# NN22_RPi_DetAdapter01_s00.net
KiCad netlist of a schematic drawn in EAGLE
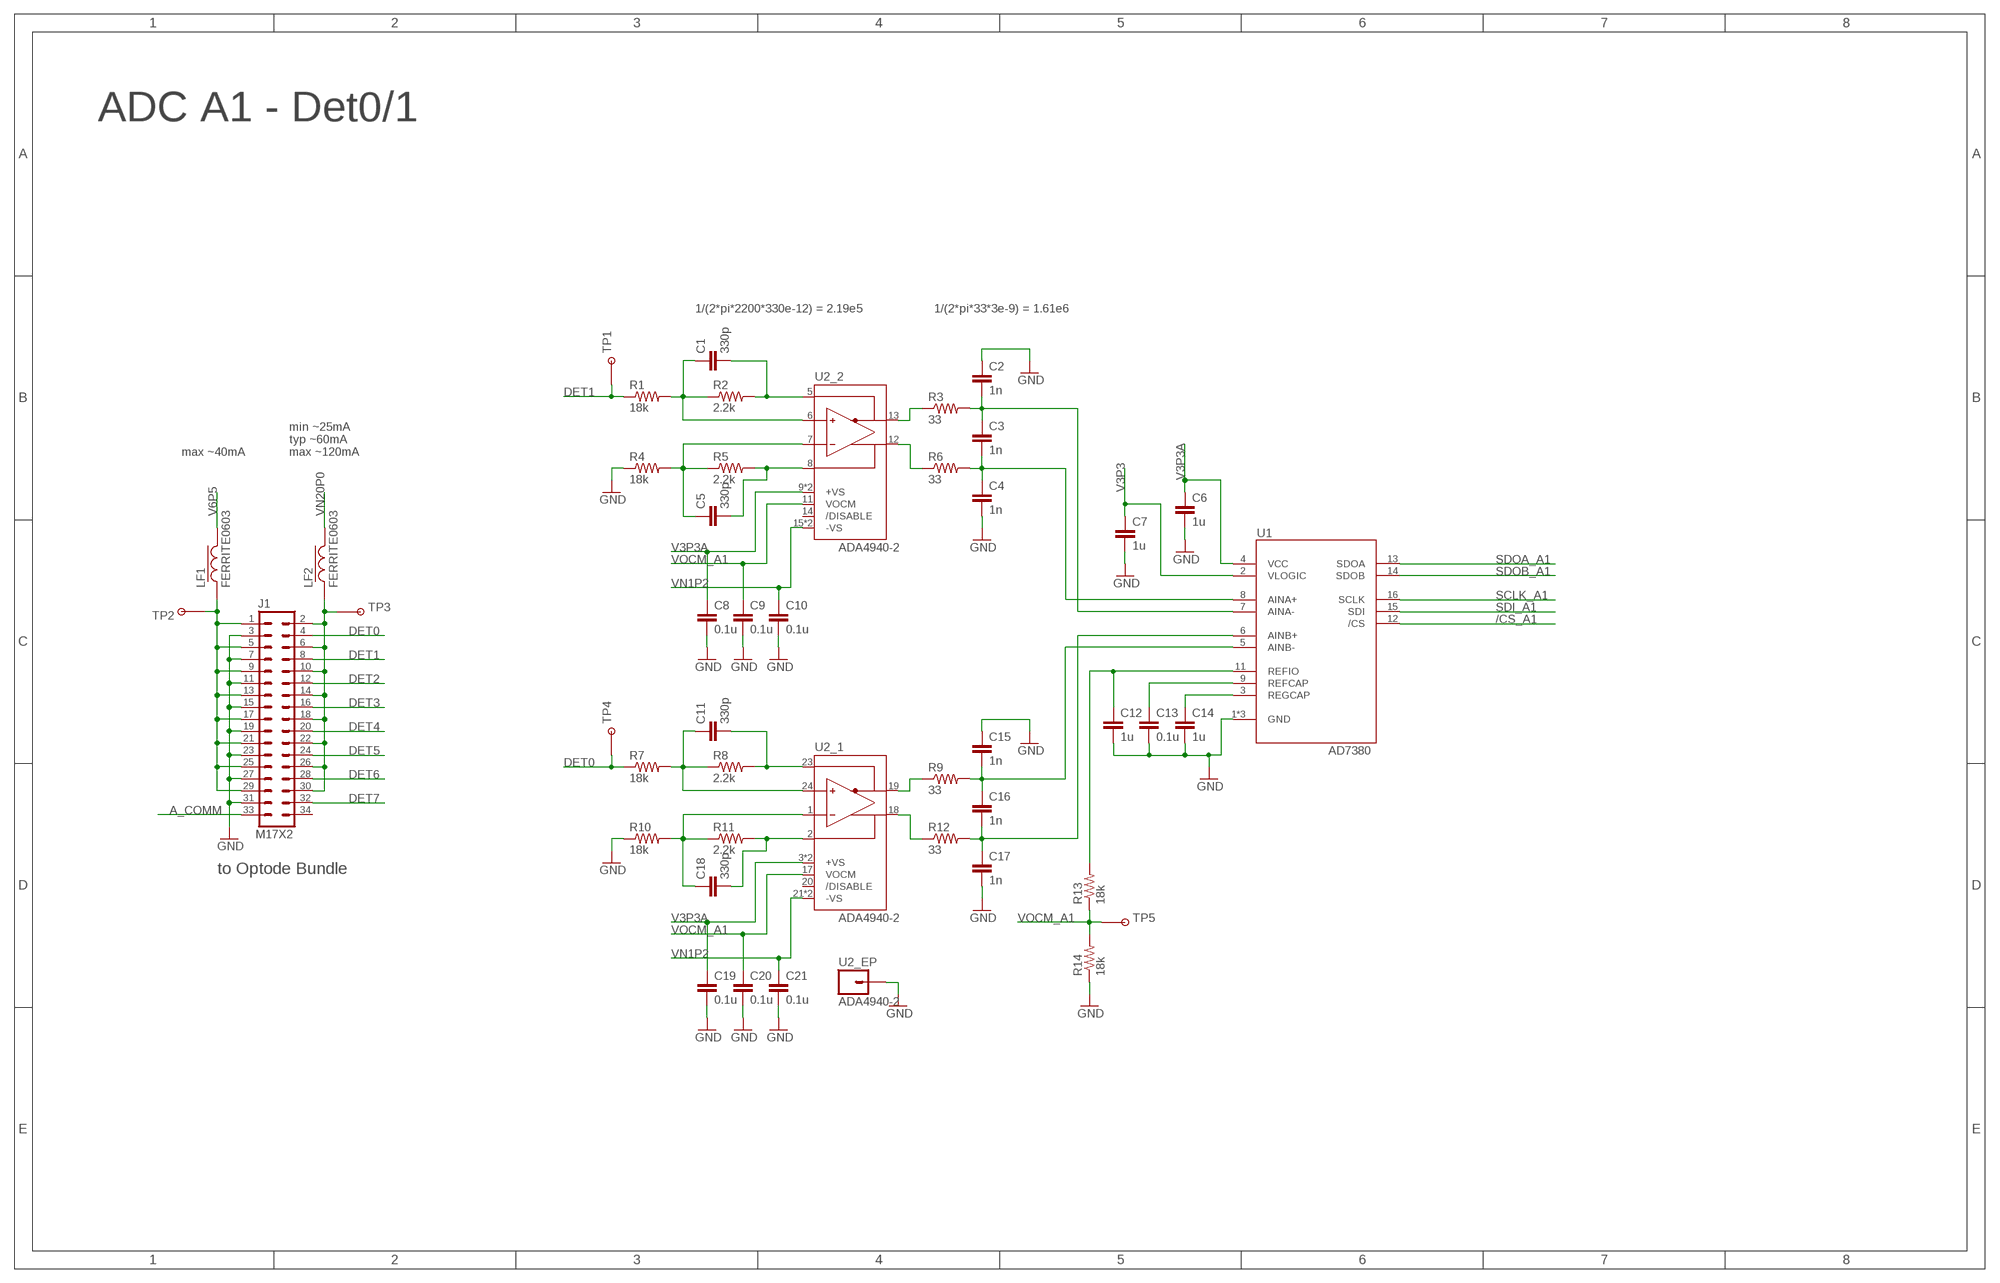
[diagram p0: schematic, sheet 1]
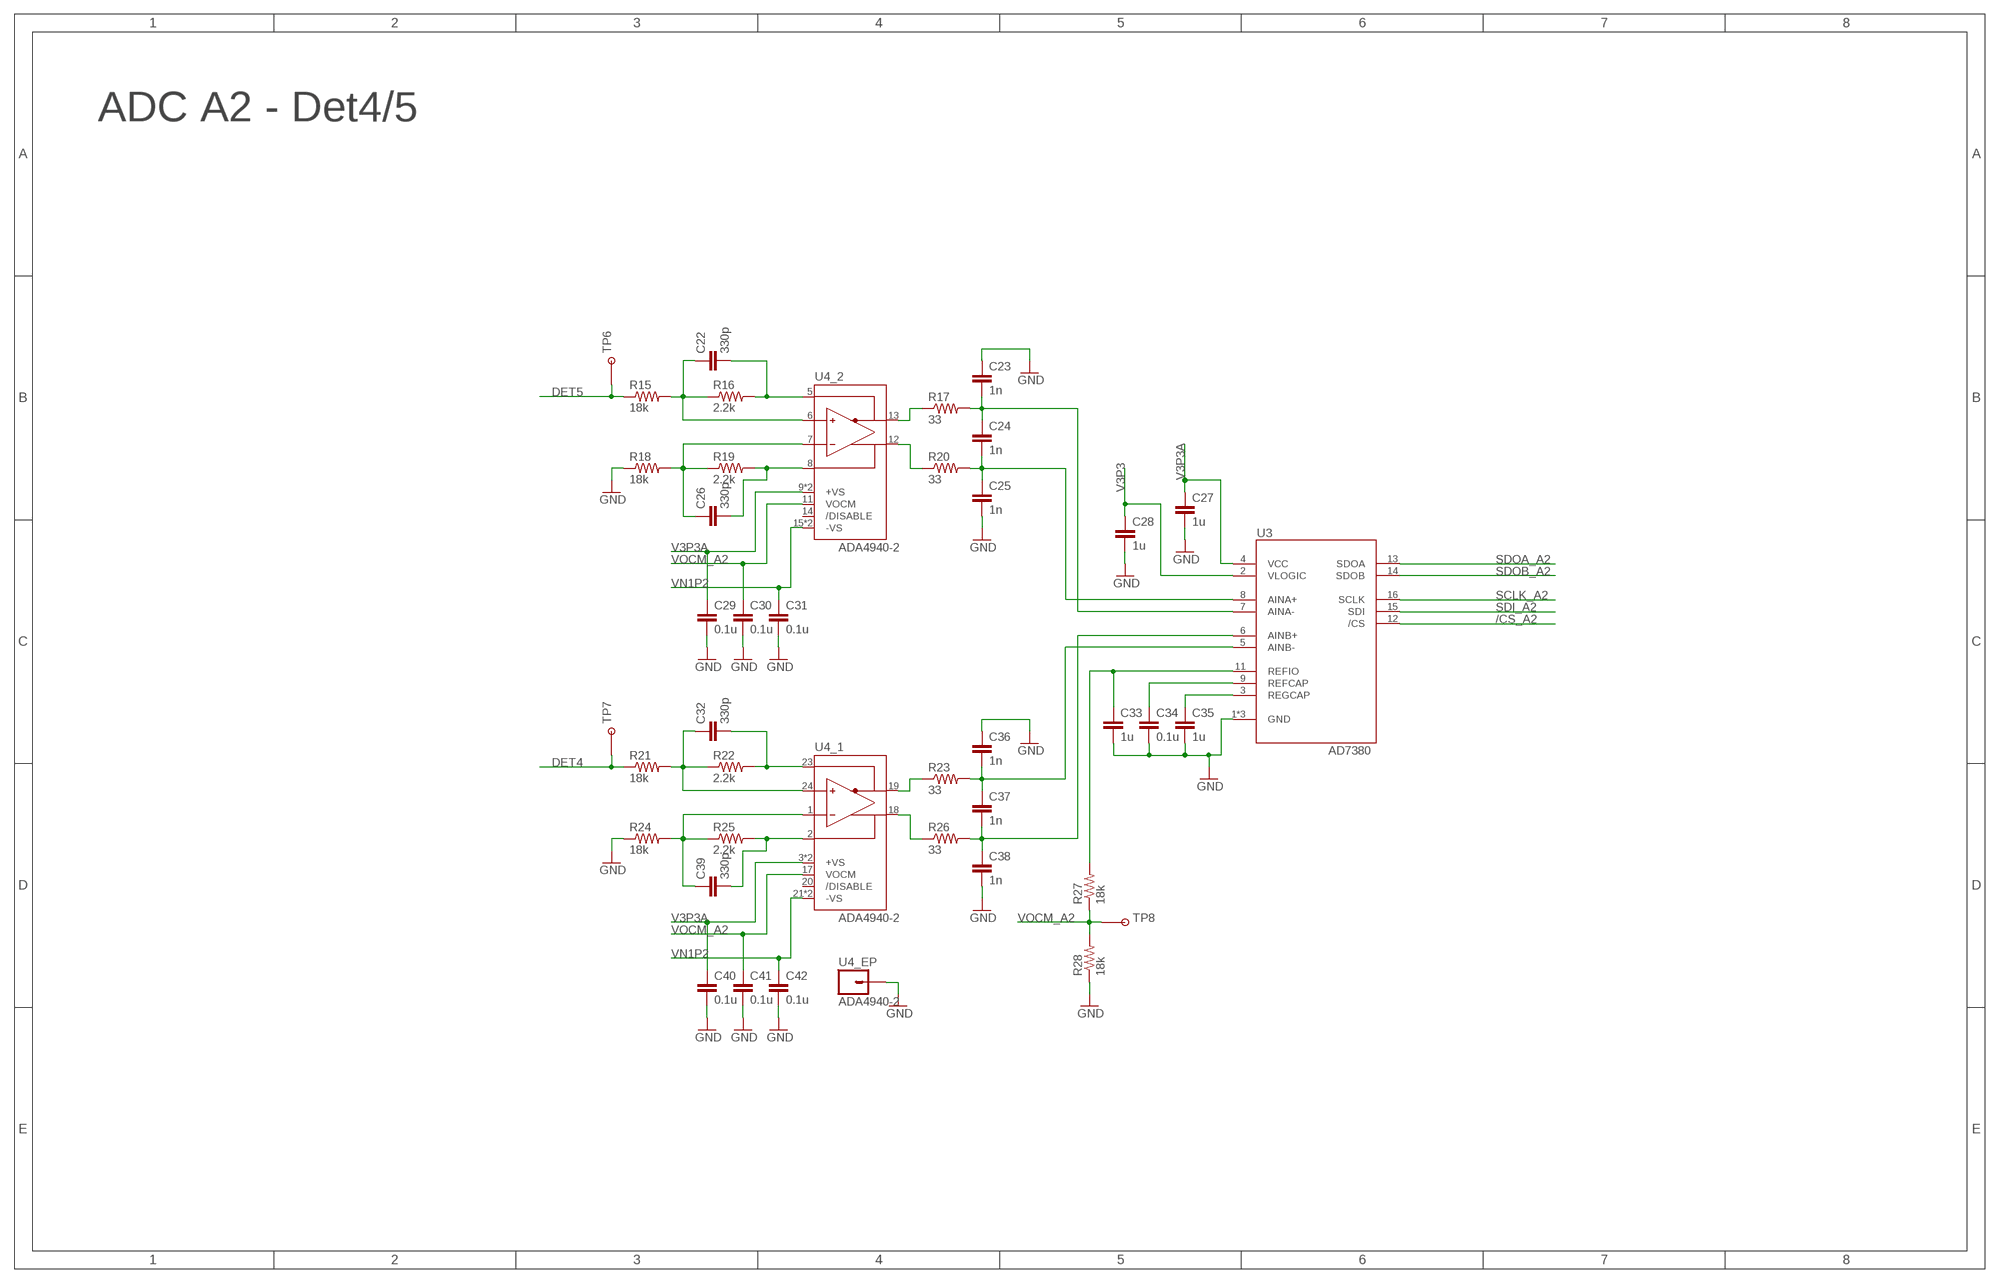
[diagram p1: schematic, sheet 2]
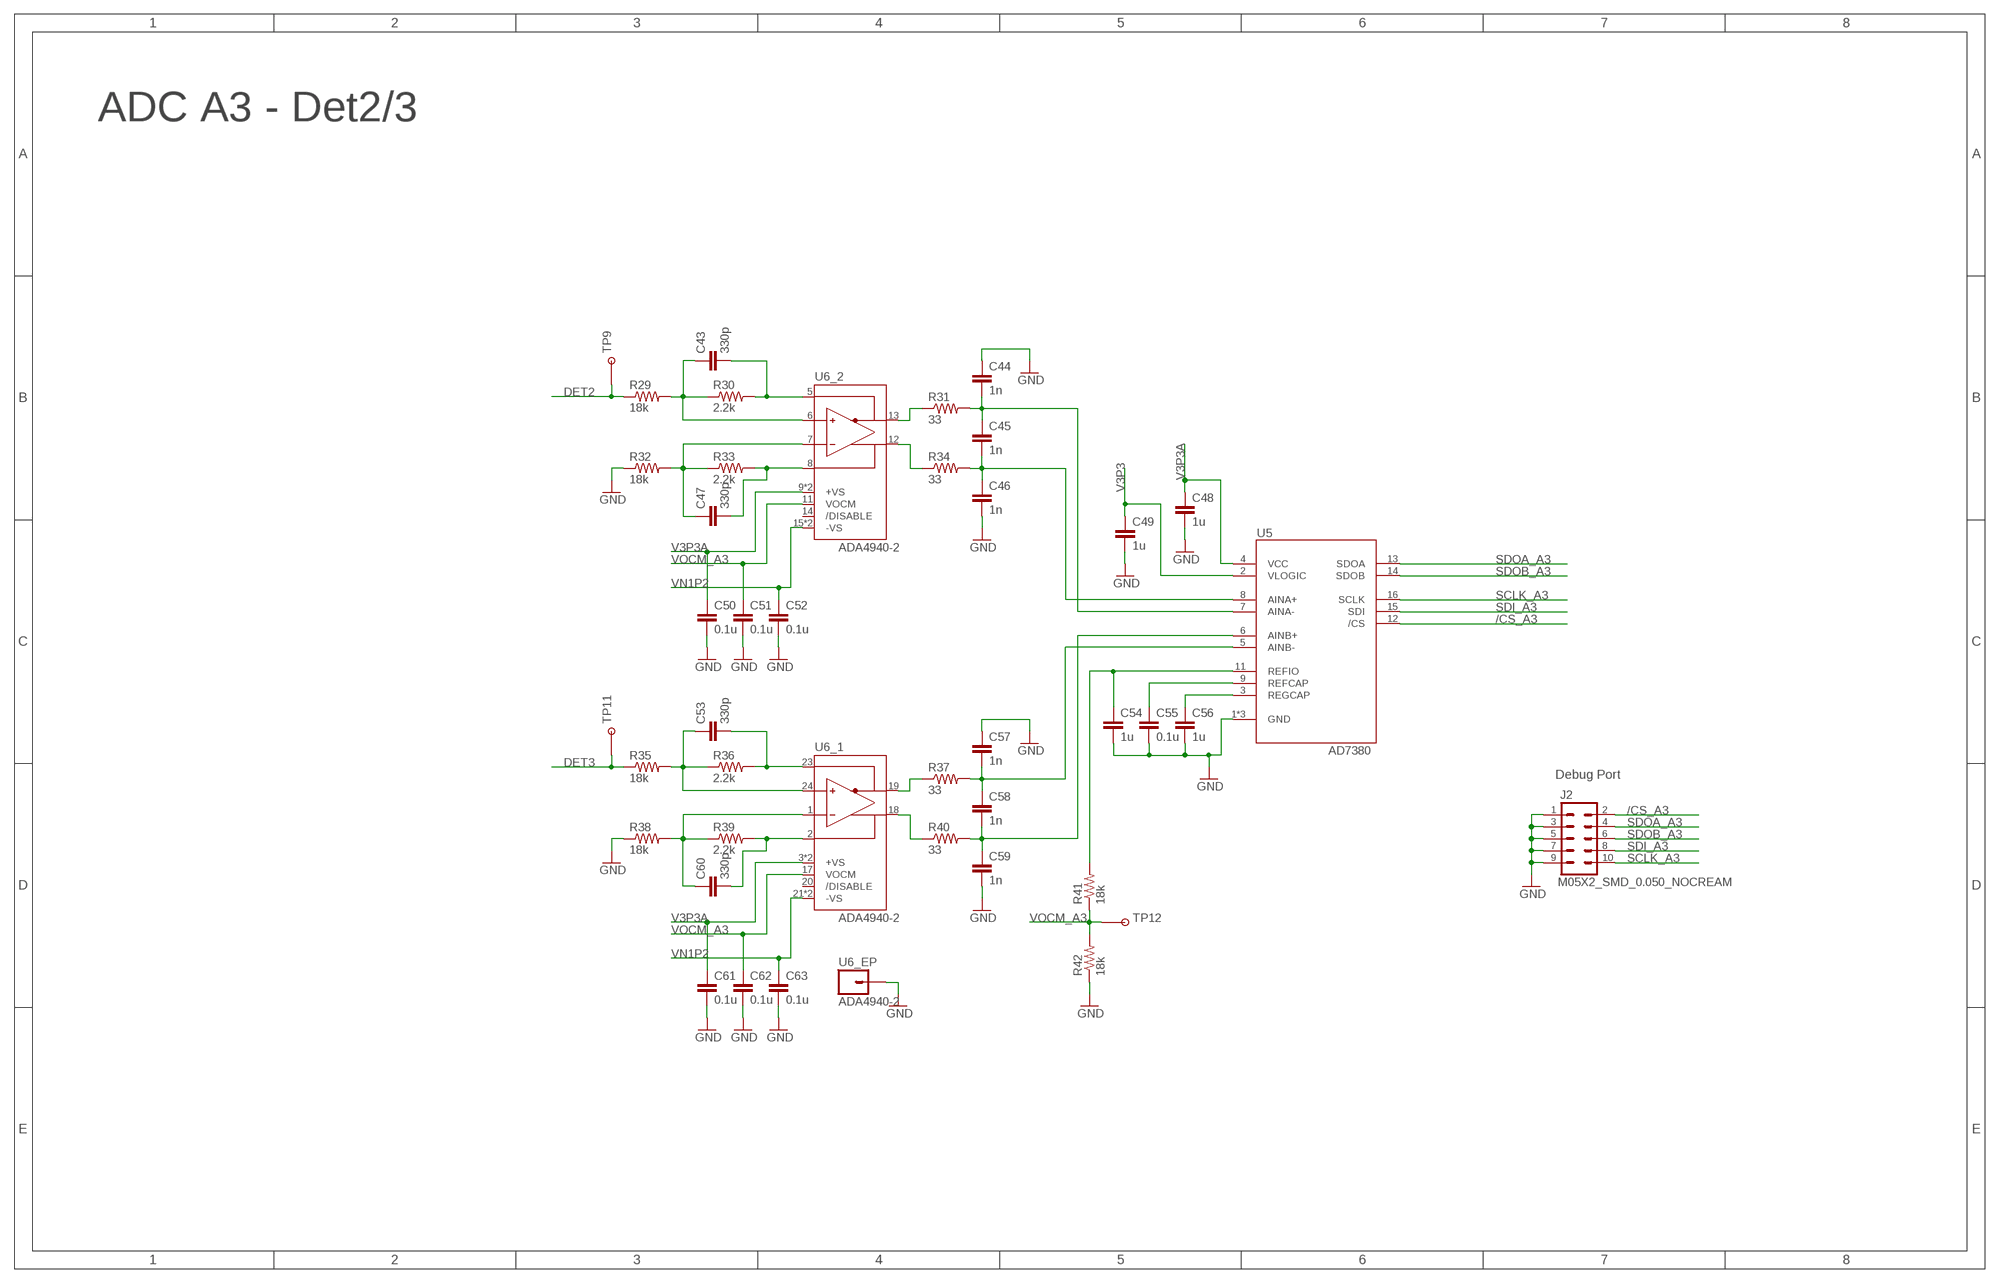
[diagram p2: schematic, sheet 3]
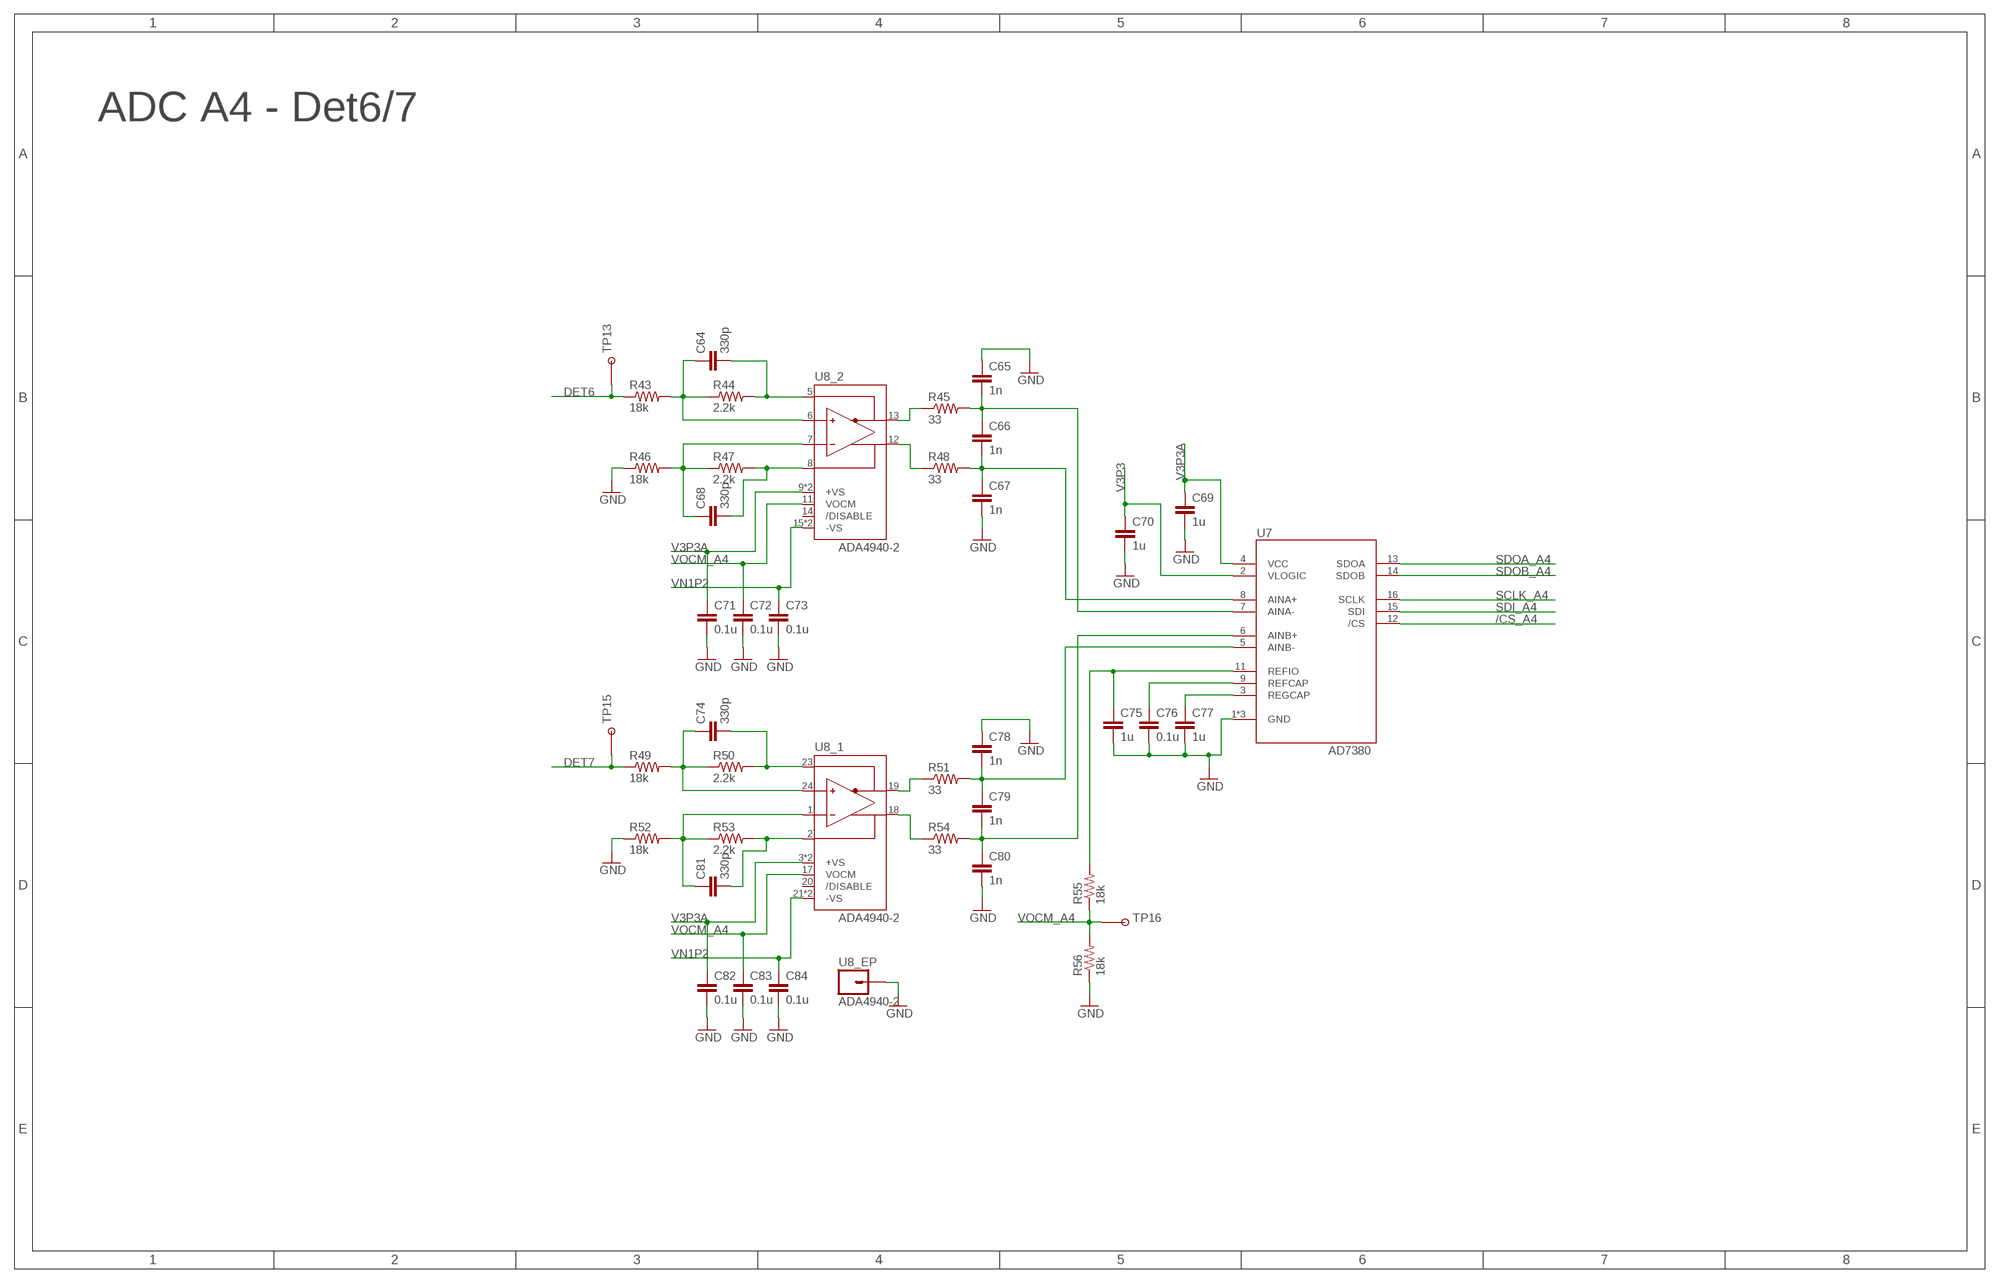
[diagram p3: schematic, sheet 4]
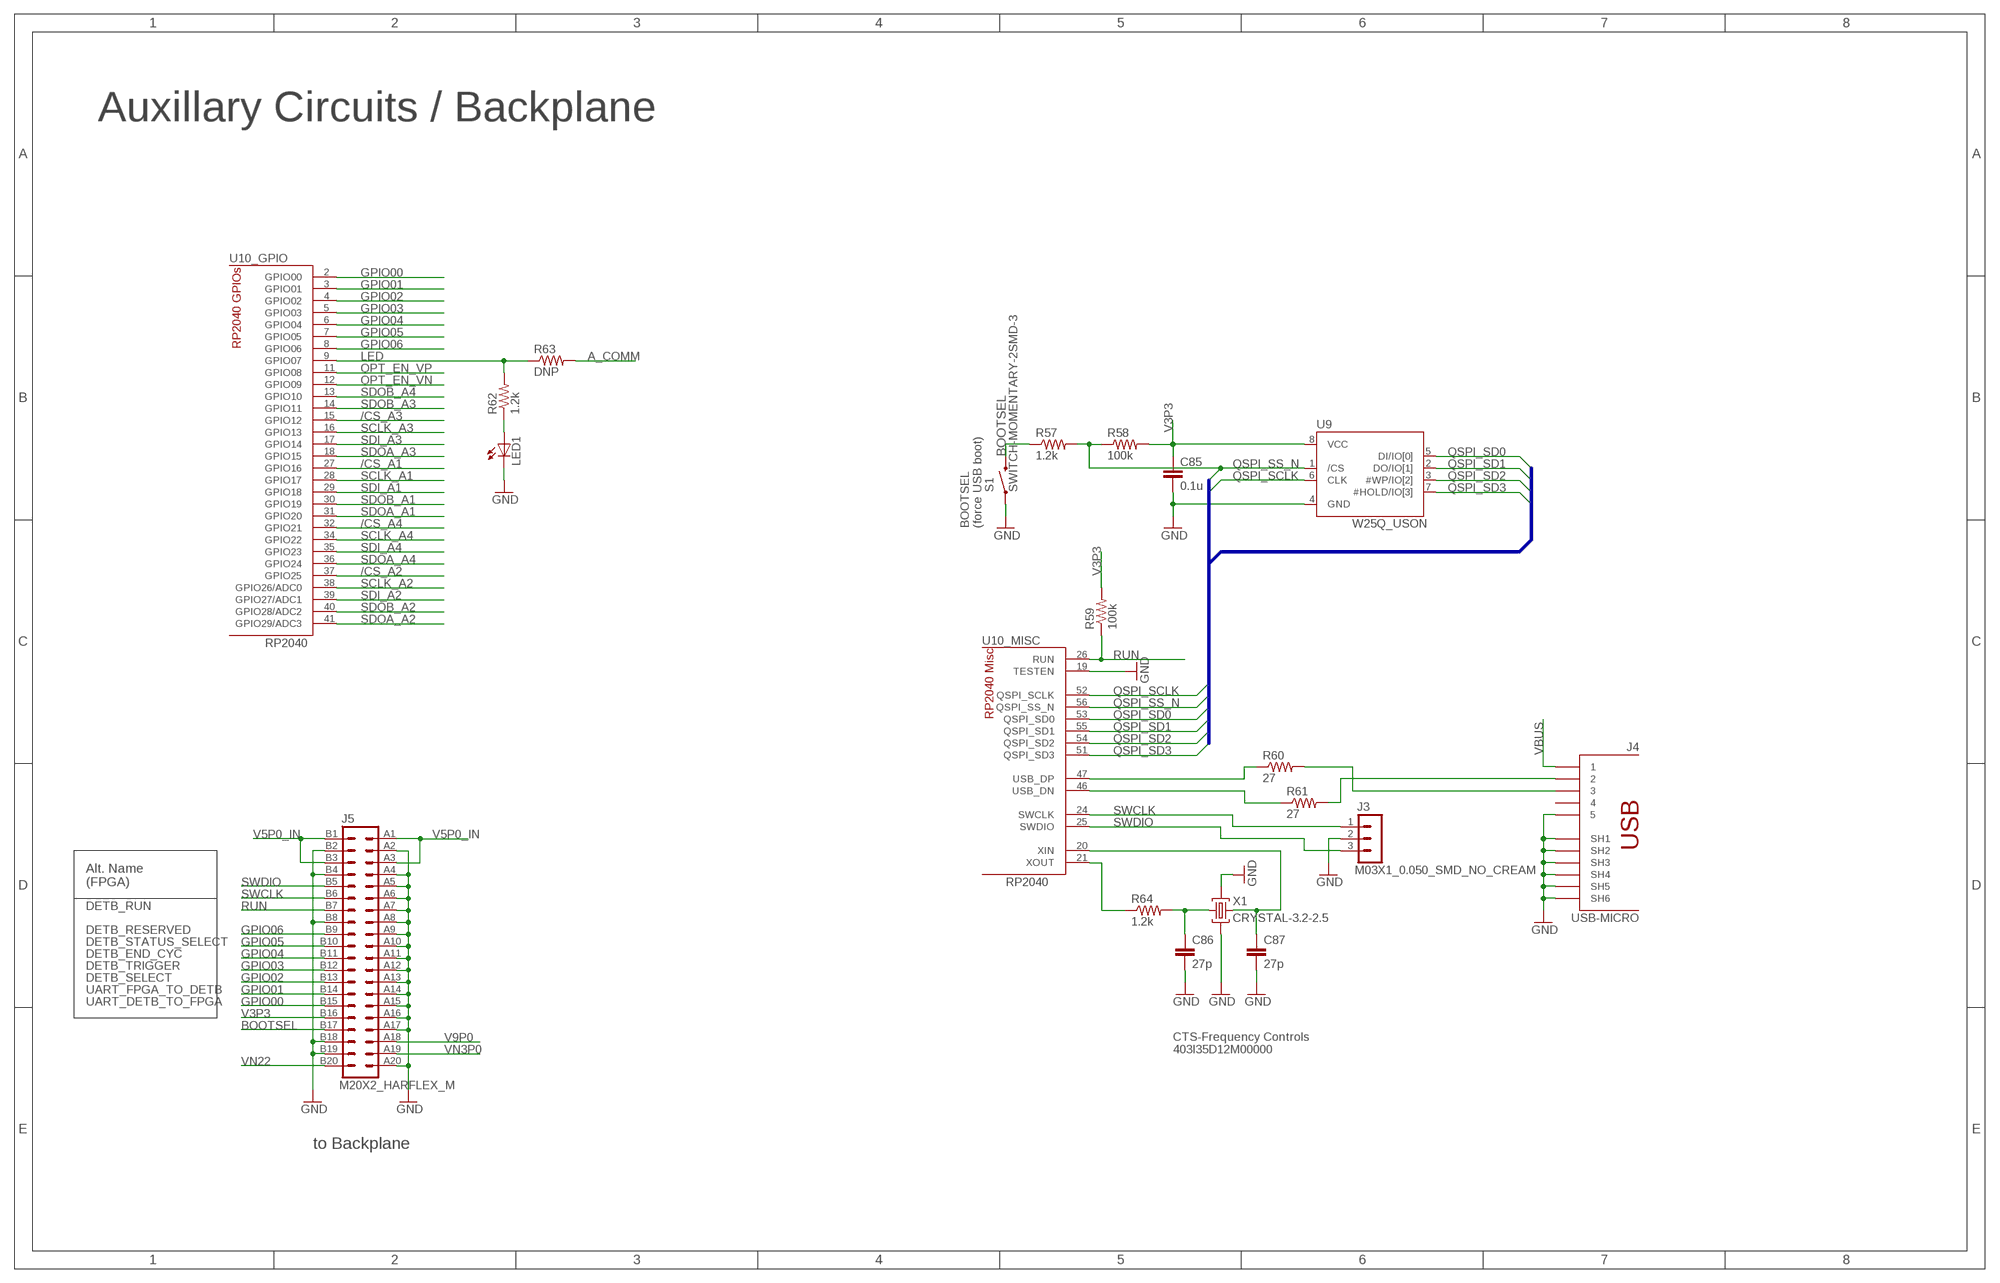
[diagram p4: schematic, sheet 5]
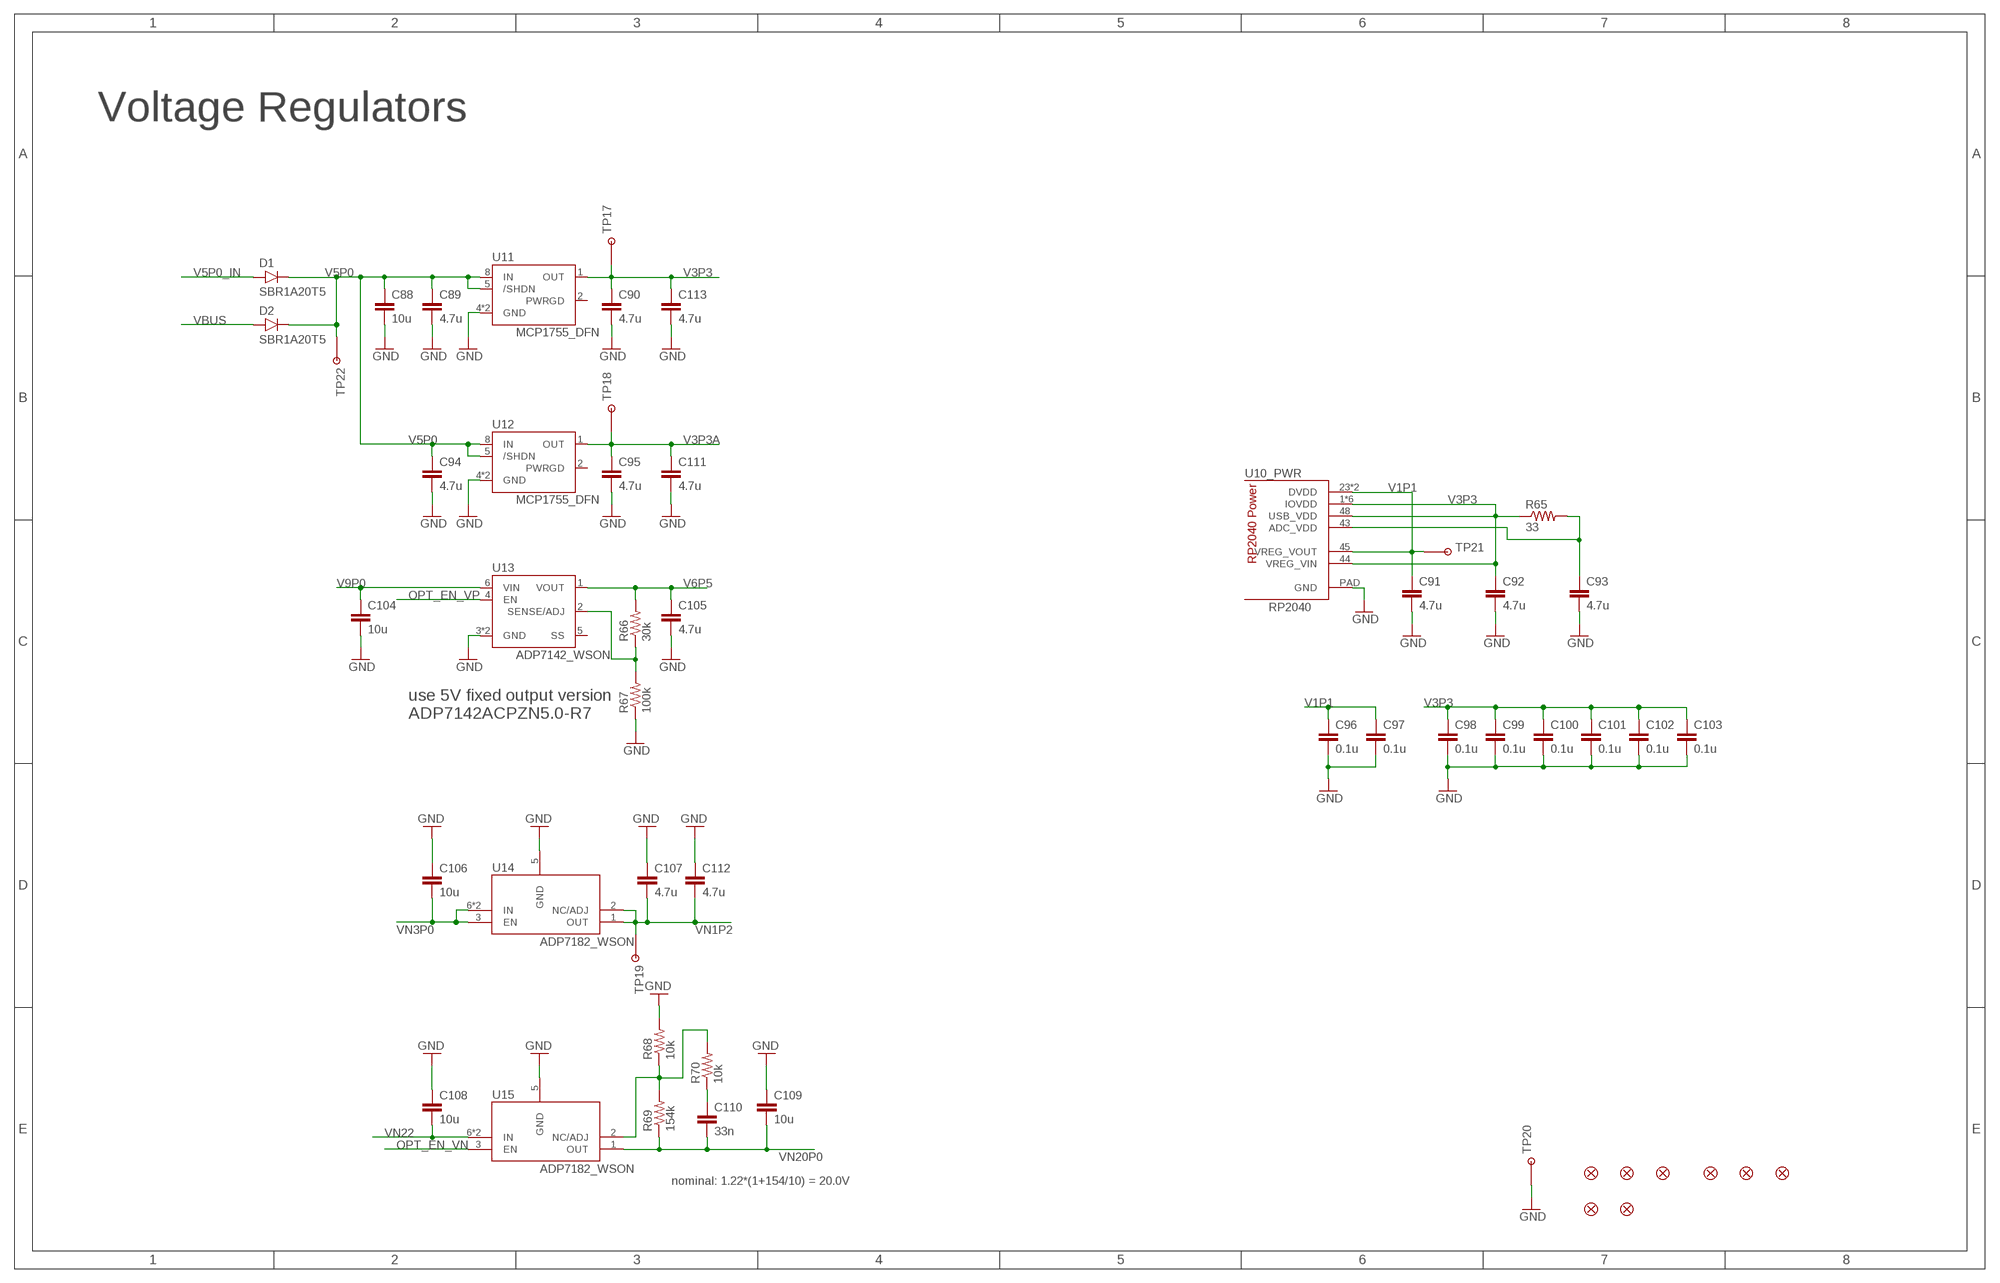
[diagram p5: schematic, sheet 6]

(export (version "E")
  (design (tool "Eeschema 10.0.6"))
  (components
    (comp (ref "C1")
      (value "330p")
      (footprint "eagle-import:0402-CAP")
      (libsource (lib "eagle-import") (part "CAP0402-CAP"))
    )
    (comp (ref "C2")
      (value "1n")
      (footprint "eagle-import:0402-CAP")
      (libsource (lib "eagle-import") (part "CAP0402-CAP"))
    )
    (comp (ref "C3")
      (value "1n")
      (footprint "eagle-import:0402-CAP")
      (libsource (lib "eagle-import") (part "CAP0402-CAP"))
    )
    (comp (ref "C4")
      (value "1n")
      (footprint "eagle-import:0402-CAP")
      (libsource (lib "eagle-import") (part "CAP0402-CAP"))
    )
    (comp (ref "C5")
      (value "330p")
      (footprint "eagle-import:0402-CAP")
      (libsource (lib "eagle-import") (part "CAP0402-CAP"))
    )
    (comp (ref "C6")
      (value "1u")
      (footprint "eagle-import:0402-CAP")
      (libsource (lib "eagle-import") (part "CAP0402-CAP"))
    )
    (comp (ref "C7")
      (value "1u")
      (footprint "eagle-import:0402-CAP")
      (libsource (lib "eagle-import") (part "CAP0402-CAP"))
    )
    (comp (ref "C8")
      (value "0.1u")
      (footprint "eagle-import:0402-CAP")
      (libsource (lib "eagle-import") (part "CAP0402-CAP"))
    )
    (comp (ref "C9")
      (value "0.1u")
      (footprint "eagle-import:0402-CAP")
      (libsource (lib "eagle-import") (part "CAP0402-CAP"))
    )
    (comp (ref "C10")
      (value "0.1u")
      (footprint "eagle-import:0402-CAP")
      (libsource (lib "eagle-import") (part "CAP0402-CAP"))
    )
    (comp (ref "C11")
      (value "330p")
      (footprint "eagle-import:0402-CAP")
      (libsource (lib "eagle-import") (part "CAP0402-CAP"))
    )
    (comp (ref "C12")
      (value "1u")
      (footprint "eagle-import:0402-CAP")
      (libsource (lib "eagle-import") (part "CAP0402-CAP"))
    )
    (comp (ref "C13")
      (value "0.1u")
      (footprint "eagle-import:0402-CAP")
      (libsource (lib "eagle-import") (part "CAP0402-CAP"))
    )
    (comp (ref "C14")
      (value "1u")
      (footprint "eagle-import:0402-CAP")
      (libsource (lib "eagle-import") (part "CAP0402-CAP"))
    )
    (comp (ref "C15")
      (value "1n")
      (footprint "eagle-import:0402-CAP")
      (libsource (lib "eagle-import") (part "CAP0402-CAP"))
    )
    (comp (ref "C16")
      (value "1n")
      (footprint "eagle-import:0402-CAP")
      (libsource (lib "eagle-import") (part "CAP0402-CAP"))
    )
    (comp (ref "C17")
      (value "1n")
      (footprint "eagle-import:0402-CAP")
      (libsource (lib "eagle-import") (part "CAP0402-CAP"))
    )
    (comp (ref "C18")
      (value "330p")
      (footprint "eagle-import:0402-CAP")
      (libsource (lib "eagle-import") (part "CAP0402-CAP"))
    )
    (comp (ref "C19")
      (value "0.1u")
      (footprint "eagle-import:0402-CAP")
      (libsource (lib "eagle-import") (part "CAP0402-CAP"))
    )
    (comp (ref "C20")
      (value "0.1u")
      (footprint "eagle-import:0402-CAP")
      (libsource (lib "eagle-import") (part "CAP0402-CAP"))
    )
    (comp (ref "C21")
      (value "0.1u")
      (footprint "eagle-import:0402-CAP")
      (libsource (lib "eagle-import") (part "CAP0402-CAP"))
    )
    (comp (ref "J1")
      (value "M17X2")
      (footprint "eagle-import:M17X2_0.050_SHF")
      (libsource (lib "eagle-import") (part "M17X2"))
    )
    (comp (ref "LF1")
      (value "FERRITE0603")
      (footprint "eagle-import:0603-FER")
      (libsource (lib "eagle-import") (part "FERRITE0603"))
    )
    (comp (ref "LF2")
      (value "FERRITE0603")
      (footprint "eagle-import:0603-FER")
      (libsource (lib "eagle-import") (part "FERRITE0603"))
    )
    (comp (ref "R1")
      (value "18k")
      (footprint "eagle-import:0402-RES")
      (libsource (lib "eagle-import") (part "RESISTOR0402-RES"))
    )
    (comp (ref "R2")
      (value "2.2k")
      (footprint "eagle-import:0402-RES")
      (libsource (lib "eagle-import") (part "RESISTOR0402-RES"))
    )
    (comp (ref "R3")
      (value "33")
      (footprint "eagle-import:0402-RES")
      (libsource (lib "eagle-import") (part "RESISTOR0402-RES"))
    )
    (comp (ref "R4")
      (value "18k")
      (footprint "eagle-import:0402-RES")
      (libsource (lib "eagle-import") (part "RESISTOR0402-RES"))
    )
    (comp (ref "R5")
      (value "2.2k")
      (footprint "eagle-import:0402-RES")
      (libsource (lib "eagle-import") (part "RESISTOR0402-RES"))
    )
    (comp (ref "R6")
      (value "33")
      (footprint "eagle-import:0402-RES")
      (libsource (lib "eagle-import") (part "RESISTOR0402-RES"))
    )
    (comp (ref "R7")
      (value "18k")
      (footprint "eagle-import:0402-RES")
      (libsource (lib "eagle-import") (part "RESISTOR0402-RES"))
    )
    (comp (ref "R8")
      (value "2.2k")
      (footprint "eagle-import:0402-RES")
      (libsource (lib "eagle-import") (part "RESISTOR0402-RES"))
    )
    (comp (ref "R9")
      (value "33")
      (footprint "eagle-import:0402-RES")
      (libsource (lib "eagle-import") (part "RESISTOR0402-RES"))
    )
    (comp (ref "R10")
      (value "18k")
      (footprint "eagle-import:0402-RES")
      (libsource (lib "eagle-import") (part "RESISTOR0402-RES"))
    )
    (comp (ref "R11")
      (value "2.2k")
      (footprint "eagle-import:0402-RES")
      (libsource (lib "eagle-import") (part "RESISTOR0402-RES"))
    )
    (comp (ref "R12")
      (value "33")
      (footprint "eagle-import:0402-RES")
      (libsource (lib "eagle-import") (part "RESISTOR0402-RES"))
    )
    (comp (ref "R13")
      (value "18k")
      (footprint "eagle-import:0402-RES")
      (libsource (lib "eagle-import") (part "RESISTOR0402-RES"))
    )
    (comp (ref "R14")
      (value "18k")
      (footprint "eagle-import:0402-RES")
      (libsource (lib "eagle-import") (part "RESISTOR0402-RES"))
    )
    (comp (ref "TP1")
      (value "TESTPOINT_ROUND")
      (footprint "eagle-import:TESTPAD_ROUND")
      (libsource (lib "eagle-import") (part "TESTPOINT_ROUND"))
    )
    (comp (ref "TP2")
      (value "TESTPOINT_ROUND")
      (footprint "eagle-import:TESTPAD_ROUND")
      (libsource (lib "eagle-import") (part "TESTPOINT_ROUND"))
    )
    (comp (ref "TP3")
      (value "TESTPOINT_ROUND")
      (footprint "eagle-import:TESTPAD_ROUND")
      (libsource (lib "eagle-import") (part "TESTPOINT_ROUND"))
    )
    (comp (ref "TP4")
      (value "TESTPOINT_ROUND")
      (footprint "eagle-import:TESTPAD_ROUND")
      (libsource (lib "eagle-import") (part "TESTPOINT_ROUND"))
    )
    (comp (ref "TP5")
      (value "TESTPOINT_ROUND")
      (footprint "eagle-import:TESTPAD_ROUND")
      (libsource (lib "eagle-import") (part "TESTPOINT_ROUND"))
    )
    (comp (ref "U1")
      (value "AD7380")
      (footprint "eagle-import:LFCSP16")
      (libsource (lib "eagle-import") (part "AD7380"))
    )
    (comp (ref "U2")
      (value "ADA4940-2")
      (footprint "eagle-import:LFCSP24")
      (libsource (lib "eagle-import") (part "ADA4940-2"))
    )
    (comp (ref "C64")
      (value "330p")
      (footprint "eagle-import:0402-CAP")
      (libsource (lib "eagle-import") (part "CAP0402-CAP"))
    )
    (comp (ref "C65")
      (value "1n")
      (footprint "eagle-import:0402-CAP")
      (libsource (lib "eagle-import") (part "CAP0402-CAP"))
    )
    (comp (ref "C66")
      (value "1n")
      (footprint "eagle-import:0402-CAP")
      (libsource (lib "eagle-import") (part "CAP0402-CAP"))
    )
    (comp (ref "C67")
      (value "1n")
      (footprint "eagle-import:0402-CAP")
      (libsource (lib "eagle-import") (part "CAP0402-CAP"))
    )
    (comp (ref "C68")
      (value "330p")
      (footprint "eagle-import:0402-CAP")
      (libsource (lib "eagle-import") (part "CAP0402-CAP"))
    )
    (comp (ref "C69")
      (value "1u")
      (footprint "eagle-import:0402-CAP")
      (libsource (lib "eagle-import") (part "CAP0402-CAP"))
    )
    (comp (ref "C70")
      (value "1u")
      (footprint "eagle-import:0402-CAP")
      (libsource (lib "eagle-import") (part "CAP0402-CAP"))
    )
    (comp (ref "C71")
      (value "0.1u")
      (footprint "eagle-import:0402-CAP")
      (libsource (lib "eagle-import") (part "CAP0402-CAP"))
    )
    (comp (ref "C72")
      (value "0.1u")
      (footprint "eagle-import:0402-CAP")
      (libsource (lib "eagle-import") (part "CAP0402-CAP"))
    )
    (comp (ref "C73")
      (value "0.1u")
      (footprint "eagle-import:0402-CAP")
      (libsource (lib "eagle-import") (part "CAP0402-CAP"))
    )
    (comp (ref "C74")
      (value "330p")
      (footprint "eagle-import:0402-CAP")
      (libsource (lib "eagle-import") (part "CAP0402-CAP"))
    )
    (comp (ref "C75")
      (value "1u")
      (footprint "eagle-import:0402-CAP")
      (libsource (lib "eagle-import") (part "CAP0402-CAP"))
    )
    (comp (ref "C76")
      (value "0.1u")
      (footprint "eagle-import:0402-CAP")
      (libsource (lib "eagle-import") (part "CAP0402-CAP"))
    )
    (comp (ref "C77")
      (value "1u")
      (footprint "eagle-import:0402-CAP")
      (libsource (lib "eagle-import") (part "CAP0402-CAP"))
    )
    (comp (ref "C78")
      (value "1n")
      (footprint "eagle-import:0402-CAP")
      (libsource (lib "eagle-import") (part "CAP0402-CAP"))
    )
    (comp (ref "C79")
      (value "1n")
      (footprint "eagle-import:0402-CAP")
      (libsource (lib "eagle-import") (part "CAP0402-CAP"))
    )
    (comp (ref "C80")
      (value "1n")
      (footprint "eagle-import:0402-CAP")
      (libsource (lib "eagle-import") (part "CAP0402-CAP"))
    )
    (comp (ref "C81")
      (value "330p")
      (footprint "eagle-import:0402-CAP")
      (libsource (lib "eagle-import") (part "CAP0402-CAP"))
    )
    (comp (ref "C82")
      (value "0.1u")
      (footprint "eagle-import:0402-CAP")
      (libsource (lib "eagle-import") (part "CAP0402-CAP"))
    )
    (comp (ref "C83")
      (value "0.1u")
      (footprint "eagle-import:0402-CAP")
      (libsource (lib "eagle-import") (part "CAP0402-CAP"))
    )
    (comp (ref "C84")
      (value "0.1u")
      (footprint "eagle-import:0402-CAP")
      (libsource (lib "eagle-import") (part "CAP0402-CAP"))
    )
    (comp (ref "R43")
      (value "18k")
      (footprint "eagle-import:0402-RES")
      (libsource (lib "eagle-import") (part "RESISTOR0402-RES"))
    )
    (comp (ref "R44")
      (value "2.2k")
      (footprint "eagle-import:0402-RES")
      (libsource (lib "eagle-import") (part "RESISTOR0402-RES"))
    )
    (comp (ref "R45")
      (value "33")
      (footprint "eagle-import:0402-RES")
      (libsource (lib "eagle-import") (part "RESISTOR0402-RES"))
    )
    (comp (ref "R46")
      (value "18k")
      (footprint "eagle-import:0402-RES")
      (libsource (lib "eagle-import") (part "RESISTOR0402-RES"))
    )
    (comp (ref "R47")
      (value "2.2k")
      (footprint "eagle-import:0402-RES")
      (libsource (lib "eagle-import") (part "RESISTOR0402-RES"))
    )
    (comp (ref "R48")
      (value "33")
      (footprint "eagle-import:0402-RES")
      (libsource (lib "eagle-import") (part "RESISTOR0402-RES"))
    )
    (comp (ref "R49")
      (value "18k")
      (footprint "eagle-import:0402-RES")
      (libsource (lib "eagle-import") (part "RESISTOR0402-RES"))
    )
    (comp (ref "R50")
      (value "2.2k")
      (footprint "eagle-import:0402-RES")
      (libsource (lib "eagle-import") (part "RESISTOR0402-RES"))
    )
    (comp (ref "R51")
      (value "33")
      (footprint "eagle-import:0402-RES")
      (libsource (lib "eagle-import") (part "RESISTOR0402-RES"))
    )
    (comp (ref "R52")
      (value "18k")
      (footprint "eagle-import:0402-RES")
      (libsource (lib "eagle-import") (part "RESISTOR0402-RES"))
    )
    (comp (ref "R53")
      (value "2.2k")
      (footprint "eagle-import:0402-RES")
      (libsource (lib "eagle-import") (part "RESISTOR0402-RES"))
    )
    (comp (ref "R54")
      (value "33")
      (footprint "eagle-import:0402-RES")
      (libsource (lib "eagle-import") (part "RESISTOR0402-RES"))
    )
    (comp (ref "R55")
      (value "18k")
      (footprint "eagle-import:0402-RES")
      (libsource (lib "eagle-import") (part "RESISTOR0402-RES"))
    )
    (comp (ref "R56")
      (value "18k")
      (footprint "eagle-import:0402-RES")
      (libsource (lib "eagle-import") (part "RESISTOR0402-RES"))
    )
    (comp (ref "TP13")
      (value "TESTPOINT_ROUND")
      (footprint "eagle-import:TESTPAD_ROUND")
      (libsource (lib "eagle-import") (part "TESTPOINT_ROUND"))
    )
    (comp (ref "TP15")
      (value "TESTPOINT_ROUND")
      (footprint "eagle-import:TESTPAD_ROUND")
      (libsource (lib "eagle-import") (part "TESTPOINT_ROUND"))
    )
    (comp (ref "TP16")
      (value "TESTPOINT_ROUND")
      (footprint "eagle-import:TESTPAD_ROUND")
      (libsource (lib "eagle-import") (part "TESTPOINT_ROUND"))
    )
    (comp (ref "U7")
      (value "AD7380")
      (footprint "eagle-import:LFCSP16")
      (libsource (lib "eagle-import") (part "AD7380"))
    )
    (comp (ref "U8")
      (value "ADA4940-2")
      (footprint "eagle-import:LFCSP24")
      (libsource (lib "eagle-import") (part "ADA4940-2"))
    )
    (comp (ref "C22")
      (value "330p")
      (footprint "eagle-import:0402-CAP")
      (libsource (lib "eagle-import") (part "CAP0402-CAP"))
    )
    (comp (ref "C23")
      (value "1n")
      (footprint "eagle-import:0402-CAP")
      (libsource (lib "eagle-import") (part "CAP0402-CAP"))
    )
    (comp (ref "C24")
      (value "1n")
      (footprint "eagle-import:0402-CAP")
      (libsource (lib "eagle-import") (part "CAP0402-CAP"))
    )
    (comp (ref "C25")
      (value "1n")
      (footprint "eagle-import:0402-CAP")
      (libsource (lib "eagle-import") (part "CAP0402-CAP"))
    )
    (comp (ref "C26")
      (value "330p")
      (footprint "eagle-import:0402-CAP")
      (libsource (lib "eagle-import") (part "CAP0402-CAP"))
    )
    (comp (ref "C27")
      (value "1u")
      (footprint "eagle-import:0402-CAP")
      (libsource (lib "eagle-import") (part "CAP0402-CAP"))
    )
    (comp (ref "C28")
      (value "1u")
      (footprint "eagle-import:0402-CAP")
      (libsource (lib "eagle-import") (part "CAP0402-CAP"))
    )
    (comp (ref "C29")
      (value "0.1u")
      (footprint "eagle-import:0402-CAP")
      (libsource (lib "eagle-import") (part "CAP0402-CAP"))
    )
    (comp (ref "C30")
      (value "0.1u")
      (footprint "eagle-import:0402-CAP")
      (libsource (lib "eagle-import") (part "CAP0402-CAP"))
    )
    (comp (ref "C31")
      (value "0.1u")
      (footprint "eagle-import:0402-CAP")
      (libsource (lib "eagle-import") (part "CAP0402-CAP"))
    )
    (comp (ref "C32")
      (value "330p")
      (footprint "eagle-import:0402-CAP")
      (libsource (lib "eagle-import") (part "CAP0402-CAP"))
    )
    (comp (ref "C33")
      (value "1u")
      (footprint "eagle-import:0402-CAP")
      (libsource (lib "eagle-import") (part "CAP0402-CAP"))
    )
    (comp (ref "C34")
      (value "0.1u")
      (footprint "eagle-import:0402-CAP")
      (libsource (lib "eagle-import") (part "CAP0402-CAP"))
    )
    (comp (ref "C35")
      (value "1u")
      (footprint "eagle-import:0402-CAP")
      (libsource (lib "eagle-import") (part "CAP0402-CAP"))
    )
    (comp (ref "C36")
      (value "1n")
      (footprint "eagle-import:0402-CAP")
      (libsource (lib "eagle-import") (part "CAP0402-CAP"))
    )
    (comp (ref "C37")
      (value "1n")
      (footprint "eagle-import:0402-CAP")
      (libsource (lib "eagle-import") (part "CAP0402-CAP"))
    )
    (comp (ref "C38")
      (value "1n")
      (footprint "eagle-import:0402-CAP")
      (libsource (lib "eagle-import") (part "CAP0402-CAP"))
    )
    (comp (ref "C39")
      (value "330p")
      (footprint "eagle-import:0402-CAP")
      (libsource (lib "eagle-import") (part "CAP0402-CAP"))
    )
    (comp (ref "C40")
      (value "0.1u")
      (footprint "eagle-import:0402-CAP")
      (libsource (lib "eagle-import") (part "CAP0402-CAP"))
    )
    (comp (ref "C41")
      (value "0.1u")
      (footprint "eagle-import:0402-CAP")
      (libsource (lib "eagle-import") (part "CAP0402-CAP"))
    )
    (comp (ref "C42")
      (value "0.1u")
      (footprint "eagle-import:0402-CAP")
      (libsource (lib "eagle-import") (part "CAP0402-CAP"))
    )
    (comp (ref "R15")
      (value "18k")
      (footprint "eagle-import:0402-RES")
      (libsource (lib "eagle-import") (part "RESISTOR0402-RES"))
    )
    (comp (ref "R16")
      (value "2.2k")
      (footprint "eagle-import:0402-RES")
      (libsource (lib "eagle-import") (part "RESISTOR0402-RES"))
    )
    (comp (ref "R17")
      (value "33")
      (footprint "eagle-import:0402-RES")
      (libsource (lib "eagle-import") (part "RESISTOR0402-RES"))
    )
    (comp (ref "R18")
      (value "18k")
      (footprint "eagle-import:0402-RES")
      (libsource (lib "eagle-import") (part "RESISTOR0402-RES"))
    )
    (comp (ref "R19")
      (value "2.2k")
      (footprint "eagle-import:0402-RES")
      (libsource (lib "eagle-import") (part "RESISTOR0402-RES"))
    )
    (comp (ref "R20")
      (value "33")
      (footprint "eagle-import:0402-RES")
      (libsource (lib "eagle-import") (part "RESISTOR0402-RES"))
    )
    (comp (ref "R21")
      (value "18k")
      (footprint "eagle-import:0402-RES")
      (libsource (lib "eagle-import") (part "RESISTOR0402-RES"))
    )
    (comp (ref "R22")
      (value "2.2k")
      (footprint "eagle-import:0402-RES")
      (libsource (lib "eagle-import") (part "RESISTOR0402-RES"))
    )
    (comp (ref "R23")
      (value "33")
      (footprint "eagle-import:0402-RES")
      (libsource (lib "eagle-import") (part "RESISTOR0402-RES"))
    )
    (comp (ref "R24")
      (value "18k")
      (footprint "eagle-import:0402-RES")
      (libsource (lib "eagle-import") (part "RESISTOR0402-RES"))
    )
    (comp (ref "R25")
      (value "2.2k")
      (footprint "eagle-import:0402-RES")
      (libsource (lib "eagle-import") (part "RESISTOR0402-RES"))
    )
    (comp (ref "R26")
      (value "33")
      (footprint "eagle-import:0402-RES")
      (libsource (lib "eagle-import") (part "RESISTOR0402-RES"))
    )
    (comp (ref "R27")
      (value "18k")
      (footprint "eagle-import:0402-RES")
      (libsource (lib "eagle-import") (part "RESISTOR0402-RES"))
    )
    (comp (ref "R28")
      (value "18k")
      (footprint "eagle-import:0402-RES")
      (libsource (lib "eagle-import") (part "RESISTOR0402-RES"))
    )
    (comp (ref "TP6")
      (value "TESTPOINT_ROUND")
      (footprint "eagle-import:TESTPAD_ROUND")
      (libsource (lib "eagle-import") (part "TESTPOINT_ROUND"))
    )
    (comp (ref "TP7")
      (value "TESTPOINT_ROUND")
      (footprint "eagle-import:TESTPAD_ROUND")
      (libsource (lib "eagle-import") (part "TESTPOINT_ROUND"))
    )
    (comp (ref "TP8")
      (value "TESTPOINT_ROUND")
      (footprint "eagle-import:TESTPAD_ROUND")
      (libsource (lib "eagle-import") (part "TESTPOINT_ROUND"))
    )
    (comp (ref "U3")
      (value "AD7380")
      (footprint "eagle-import:LFCSP16")
      (libsource (lib "eagle-import") (part "AD7380"))
    )
    (comp (ref "U4")
      (value "ADA4940-2")
      (footprint "eagle-import:LFCSP24")
      (libsource (lib "eagle-import") (part "ADA4940-2"))
    )
    (comp (ref "C43")
      (value "330p")
      (footprint "eagle-import:0402-CAP")
      (libsource (lib "eagle-import") (part "CAP0402-CAP"))
    )
    (comp (ref "C44")
      (value "1n")
      (footprint "eagle-import:0402-CAP")
      (libsource (lib "eagle-import") (part "CAP0402-CAP"))
    )
    (comp (ref "C45")
      (value "1n")
      (footprint "eagle-import:0402-CAP")
      (libsource (lib "eagle-import") (part "CAP0402-CAP"))
    )
    (comp (ref "C46")
      (value "1n")
      (footprint "eagle-import:0402-CAP")
      (libsource (lib "eagle-import") (part "CAP0402-CAP"))
    )
    (comp (ref "C47")
      (value "330p")
      (footprint "eagle-import:0402-CAP")
      (libsource (lib "eagle-import") (part "CAP0402-CAP"))
    )
    (comp (ref "C48")
      (value "1u")
      (footprint "eagle-import:0402-CAP")
      (libsource (lib "eagle-import") (part "CAP0402-CAP"))
    )
    (comp (ref "C49")
      (value "1u")
      (footprint "eagle-import:0402-CAP")
      (libsource (lib "eagle-import") (part "CAP0402-CAP"))
    )
    (comp (ref "C50")
      (value "0.1u")
      (footprint "eagle-import:0402-CAP")
      (libsource (lib "eagle-import") (part "CAP0402-CAP"))
    )
    (comp (ref "C51")
      (value "0.1u")
      (footprint "eagle-import:0402-CAP")
      (libsource (lib "eagle-import") (part "CAP0402-CAP"))
    )
    (comp (ref "C52")
      (value "0.1u")
      (footprint "eagle-import:0402-CAP")
      (libsource (lib "eagle-import") (part "CAP0402-CAP"))
    )
    (comp (ref "C53")
      (value "330p")
      (footprint "eagle-import:0402-CAP")
      (libsource (lib "eagle-import") (part "CAP0402-CAP"))
    )
    (comp (ref "C54")
      (value "1u")
      (footprint "eagle-import:0402-CAP")
      (libsource (lib "eagle-import") (part "CAP0402-CAP"))
    )
    (comp (ref "C55")
      (value "0.1u")
      (footprint "eagle-import:0402-CAP")
      (libsource (lib "eagle-import") (part "CAP0402-CAP"))
    )
    (comp (ref "C56")
      (value "1u")
      (footprint "eagle-import:0402-CAP")
      (libsource (lib "eagle-import") (part "CAP0402-CAP"))
    )
    (comp (ref "C57")
      (value "1n")
      (footprint "eagle-import:0402-CAP")
      (libsource (lib "eagle-import") (part "CAP0402-CAP"))
    )
    (comp (ref "C58")
      (value "1n")
      (footprint "eagle-import:0402-CAP")
      (libsource (lib "eagle-import") (part "CAP0402-CAP"))
    )
    (comp (ref "C59")
      (value "1n")
      (footprint "eagle-import:0402-CAP")
      (libsource (lib "eagle-import") (part "CAP0402-CAP"))
    )
    (comp (ref "C60")
      (value "330p")
      (footprint "eagle-import:0402-CAP")
      (libsource (lib "eagle-import") (part "CAP0402-CAP"))
    )
    (comp (ref "C61")
      (value "0.1u")
      (footprint "eagle-import:0402-CAP")
      (libsource (lib "eagle-import") (part "CAP0402-CAP"))
    )
    (comp (ref "C62")
      (value "0.1u")
      (footprint "eagle-import:0402-CAP")
      (libsource (lib "eagle-import") (part "CAP0402-CAP"))
    )
    (comp (ref "C63")
      (value "0.1u")
      (footprint "eagle-import:0402-CAP")
      (libsource (lib "eagle-import") (part "CAP0402-CAP"))
    )
    (comp (ref "J2")
      (value "M05X2_SMD_0.050_NOCREAM")
      (footprint "eagle-import:M05X2_0.050_SMD_NO_CREAM")
      (libsource (lib "eagle-import") (part "M05X2_SMD_0.050_NOCREAM"))
    )
    (comp (ref "R29")
      (value "18k")
      (footprint "eagle-import:0402-RES")
      (libsource (lib "eagle-import") (part "RESISTOR0402-RES"))
    )
    (comp (ref "R30")
      (value "2.2k")
      (footprint "eagle-import:0402-RES")
      (libsource (lib "eagle-import") (part "RESISTOR0402-RES"))
    )
    (comp (ref "R31")
      (value "33")
      (footprint "eagle-import:0402-RES")
      (libsource (lib "eagle-import") (part "RESISTOR0402-RES"))
    )
    (comp (ref "R32")
      (value "18k")
      (footprint "eagle-import:0402-RES")
      (libsource (lib "eagle-import") (part "RESISTOR0402-RES"))
    )
    (comp (ref "R33")
      (value "2.2k")
      (footprint "eagle-import:0402-RES")
      (libsource (lib "eagle-import") (part "RESISTOR0402-RES"))
    )
    (comp (ref "R34")
      (value "33")
      (footprint "eagle-import:0402-RES")
      (libsource (lib "eagle-import") (part "RESISTOR0402-RES"))
    )
    (comp (ref "R35")
      (value "18k")
      (footprint "eagle-import:0402-RES")
      (libsource (lib "eagle-import") (part "RESISTOR0402-RES"))
    )
    (comp (ref "R36")
      (value "2.2k")
      (footprint "eagle-import:0402-RES")
      (libsource (lib "eagle-import") (part "RESISTOR0402-RES"))
    )
    (comp (ref "R37")
      (value "33")
      (footprint "eagle-import:0402-RES")
      (libsource (lib "eagle-import") (part "RESISTOR0402-RES"))
    )
    (comp (ref "R38")
      (value "18k")
      (footprint "eagle-import:0402-RES")
      (libsource (lib "eagle-import") (part "RESISTOR0402-RES"))
    )
    (comp (ref "R39")
      (value "2.2k")
      (footprint "eagle-import:0402-RES")
      (libsource (lib "eagle-import") (part "RESISTOR0402-RES"))
    )
    (comp (ref "R40")
      (value "33")
      (footprint "eagle-import:0402-RES")
      (libsource (lib "eagle-import") (part "RESISTOR0402-RES"))
    )
    (comp (ref "R41")
      (value "18k")
      (footprint "eagle-import:0402-RES")
      (libsource (lib "eagle-import") (part "RESISTOR0402-RES"))
    )
    (comp (ref "R42")
      (value "18k")
      (footprint "eagle-import:0402-RES")
      (libsource (lib "eagle-import") (part "RESISTOR0402-RES"))
    )
    (comp (ref "TP9")
      (value "TESTPOINT_ROUND")
      (footprint "eagle-import:TESTPAD_ROUND")
      (libsource (lib "eagle-import") (part "TESTPOINT_ROUND"))
    )
    (comp (ref "TP11")
      (value "TESTPOINT_ROUND")
      (footprint "eagle-import:TESTPAD_ROUND")
      (libsource (lib "eagle-import") (part "TESTPOINT_ROUND"))
    )
    (comp (ref "TP12")
      (value "TESTPOINT_ROUND")
      (footprint "eagle-import:TESTPAD_ROUND")
      (libsource (lib "eagle-import") (part "TESTPOINT_ROUND"))
    )
    (comp (ref "U5")
      (value "AD7380")
      (footprint "eagle-import:LFCSP16")
      (libsource (lib "eagle-import") (part "AD7380"))
    )
    (comp (ref "U6")
      (value "ADA4940-2")
      (footprint "eagle-import:LFCSP24")
      (libsource (lib "eagle-import") (part "ADA4940-2"))
    )
    (comp (ref "C88")
      (value "10u")
      (footprint "eagle-import:0603-CAP")
      (libsource (lib "eagle-import") (part "CAP0603-CAP"))
    )
    (comp (ref "C89")
      (value "4.7u")
      (footprint "eagle-import:0402-CAP")
      (libsource (lib "eagle-import") (part "CAP0402-CAP"))
    )
    (comp (ref "C90")
      (value "4.7u")
      (footprint "eagle-import:0402-CAP")
      (libsource (lib "eagle-import") (part "CAP0402-CAP"))
    )
    (comp (ref "C91")
      (value "4.7u")
      (footprint "eagle-import:0402-CAP")
      (libsource (lib "eagle-import") (part "CAP0402-CAP"))
    )
    (comp (ref "C92")
      (value "4.7u")
      (footprint "eagle-import:0402-CAP")
      (libsource (lib "eagle-import") (part "CAP0402-CAP"))
    )
    (comp (ref "C93")
      (value "4.7u")
      (footprint "eagle-import:0402-CAP")
      (libsource (lib "eagle-import") (part "CAP0402-CAP"))
    )
    (comp (ref "C94")
      (value "4.7u")
      (footprint "eagle-import:0402-CAP")
      (libsource (lib "eagle-import") (part "CAP0402-CAP"))
    )
    (comp (ref "C95")
      (value "4.7u")
      (footprint "eagle-import:0402-CAP")
      (libsource (lib "eagle-import") (part "CAP0402-CAP"))
    )
    (comp (ref "C96")
      (value "0.1u")
      (footprint "eagle-import:0402-CAP")
      (libsource (lib "eagle-import") (part "CAP0402-CAP"))
    )
    (comp (ref "C97")
      (value "0.1u")
      (footprint "eagle-import:0402-CAP")
      (libsource (lib "eagle-import") (part "CAP0402-CAP"))
    )
    (comp (ref "C98")
      (value "0.1u")
      (footprint "eagle-import:0402-CAP")
      (libsource (lib "eagle-import") (part "CAP0402-CAP"))
    )
    (comp (ref "C99")
      (value "0.1u")
      (footprint "eagle-import:0402-CAP")
      (libsource (lib "eagle-import") (part "CAP0402-CAP"))
    )
    (comp (ref "C100")
      (value "0.1u")
      (footprint "eagle-import:0402-CAP")
      (libsource (lib "eagle-import") (part "CAP0402-CAP"))
    )
    (comp (ref "C101")
      (value "0.1u")
      (footprint "eagle-import:0402-CAP")
      (libsource (lib "eagle-import") (part "CAP0402-CAP"))
    )
    (comp (ref "C102")
      (value "0.1u")
      (footprint "eagle-import:0402-CAP")
      (libsource (lib "eagle-import") (part "CAP0402-CAP"))
    )
    (comp (ref "C103")
      (value "0.1u")
      (footprint "eagle-import:0402-CAP")
      (libsource (lib "eagle-import") (part "CAP0402-CAP"))
    )
    (comp (ref "C104")
      (value "10u")
      (footprint "eagle-import:0603-CAP")
      (libsource (lib "eagle-import") (part "CAP0603-CAP"))
    )
    (comp (ref "C105")
      (value "4.7u")
      (footprint "eagle-import:0402-CAP")
      (libsource (lib "eagle-import") (part "CAP0402-CAP"))
    )
    (comp (ref "C106")
      (value "10u")
      (footprint "eagle-import:0603-CAP")
      (libsource (lib "eagle-import") (part "CAP0603-CAP"))
    )
    (comp (ref "C107")
      (value "4.7u")
      (footprint "eagle-import:0402-CAP")
      (libsource (lib "eagle-import") (part "CAP0402-CAP"))
    )
    (comp (ref "C108")
      (value "10u")
      (footprint "eagle-import:0603-CAP")
      (libsource (lib "eagle-import") (part "CAP0603-CAP"))
    )
    (comp (ref "C109")
      (value "10u")
      (footprint "eagle-import:0603-CAP")
      (libsource (lib "eagle-import") (part "CAP0603-CAP"))
    )
    (comp (ref "C110")
      (value "33n")
      (footprint "eagle-import:0402-CAP")
      (libsource (lib "eagle-import") (part "CAP0402-CAP"))
    )
    (comp (ref "C111")
      (value "4.7u")
      (footprint "eagle-import:0402-CAP")
      (libsource (lib "eagle-import") (part "CAP0402-CAP"))
    )
    (comp (ref "C112")
      (value "4.7u")
      (footprint "eagle-import:0402-CAP")
      (libsource (lib "eagle-import") (part "CAP0402-CAP"))
    )
    (comp (ref "C113")
      (value "4.7u")
      (footprint "eagle-import:0402-CAP")
      (libsource (lib "eagle-import") (part "CAP0402-CAP"))
    )
    (comp (ref "D1")
      (value "SBR1A20T5")
      (footprint "eagle-import:SOD523")
      (libsource (lib "eagle-import") (part "DIODE_SOD523"))
    )
    (comp (ref "D2")
      (value "SBR1A20T5")
      (footprint "eagle-import:SOD523")
      (libsource (lib "eagle-import") (part "DIODE_SOD523"))
    )
    (comp (ref "FID1")
      (value "FIDUCIALUFIDUCIAL")
      (footprint "eagle-import:MICRO-FIDUCIAL")
      (libsource (lib "eagle-import") (part "FIDUCIALUFIDUCIAL"))
    )
    (comp (ref "FID2")
      (value "FIDUCIALUFIDUCIAL")
      (footprint "eagle-import:MICRO-FIDUCIAL")
      (libsource (lib "eagle-import") (part "FIDUCIALUFIDUCIAL"))
    )
    (comp (ref "FID3")
      (value "FIDUCIALUFIDUCIAL")
      (footprint "eagle-import:MICRO-FIDUCIAL")
      (libsource (lib "eagle-import") (part "FIDUCIALUFIDUCIAL"))
    )
    (comp (ref "FID4")
      (value "FIDUCIALUFIDUCIAL")
      (footprint "eagle-import:MICRO-FIDUCIAL")
      (libsource (lib "eagle-import") (part "FIDUCIALUFIDUCIAL"))
    )
    (comp (ref "FID5")
      (value "FIDUCIALUFIDUCIAL")
      (footprint "eagle-import:MICRO-FIDUCIAL")
      (libsource (lib "eagle-import") (part "FIDUCIALUFIDUCIAL"))
    )
    (comp (ref "FID6")
      (value "FIDUCIALUFIDUCIAL")
      (footprint "eagle-import:MICRO-FIDUCIAL")
      (libsource (lib "eagle-import") (part "FIDUCIALUFIDUCIAL"))
    )
    (comp (ref "FID7")
      (value "FIDUCIALUFIDUCIAL")
      (footprint "eagle-import:MICRO-FIDUCIAL")
      (libsource (lib "eagle-import") (part "FIDUCIALUFIDUCIAL"))
    )
    (comp (ref "FID8")
      (value "FIDUCIALUFIDUCIAL")
      (footprint "eagle-import:MICRO-FIDUCIAL")
      (libsource (lib "eagle-import") (part "FIDUCIALUFIDUCIAL"))
    )
    (comp (ref "R65")
      (value "33")
      (footprint "eagle-import:0402-RES")
      (libsource (lib "eagle-import") (part "RESISTOR0402-RES"))
    )
    (comp (ref "R66")
      (value "30k")
      (footprint "eagle-import:0402-RES")
      (libsource (lib "eagle-import") (part "RESISTOR0402-RES"))
    )
    (comp (ref "R67")
      (value "100k")
      (footprint "eagle-import:0402-RES")
      (libsource (lib "eagle-import") (part "RESISTOR0402-RES"))
    )
    (comp (ref "R68")
      (value "10k")
      (footprint "eagle-import:0402-RES")
      (libsource (lib "eagle-import") (part "RESISTOR0402-RES"))
    )
    (comp (ref "R69")
      (value "154k")
      (footprint "eagle-import:0402-RES")
      (libsource (lib "eagle-import") (part "RESISTOR0402-RES"))
    )
    (comp (ref "R70")
      (value "10k")
      (footprint "eagle-import:0402-RES")
      (libsource (lib "eagle-import") (part "RESISTOR0402-RES"))
    )
    (comp (ref "TP17")
      (value "TESTPOINT_ROUND")
      (footprint "eagle-import:TESTPAD_ROUND")
      (libsource (lib "eagle-import") (part "TESTPOINT_ROUND"))
    )
    (comp (ref "TP18")
      (value "TESTPOINT_ROUND")
      (footprint "eagle-import:TESTPAD_ROUND")
      (libsource (lib "eagle-import") (part "TESTPOINT_ROUND"))
    )
    (comp (ref "TP19")
      (value "TESTPOINT_ROUND")
      (footprint "eagle-import:TESTPAD_ROUND")
      (libsource (lib "eagle-import") (part "TESTPOINT_ROUND"))
    )
    (comp (ref "TP20")
      (value "TESTPOINT1X01")
      (footprint "eagle-import:1X01")
      (libsource (lib "eagle-import") (part "TESTPOINT1X01"))
    )
    (comp (ref "TP21")
      (value "TESTPOINTPADSMALL")
      (footprint "eagle-import:TESTPAD_SMALL")
      (libsource (lib "eagle-import") (part "TESTPOINTPADSMALL"))
    )
    (comp (ref "TP22")
      (value "TESTPOINT_ROUND")
      (footprint "eagle-import:TESTPAD_ROUND")
      (libsource (lib "eagle-import") (part "TESTPOINT_ROUND"))
    )
    (comp (ref "U10")
      (value "RP2040")
      (footprint "eagle-import:QFN-56_EP")
      (libsource (lib "eagle-import") (part "RP2040"))
    )
    (comp (ref "U11")
      (value "MCP1755_DFN")
      (footprint "eagle-import:DFN8_2X3MM")
      (libsource (lib "eagle-import") (part "MCP1755_DFN"))
    )
    (comp (ref "U12")
      (value "MCP1755_DFN")
      (footprint "eagle-import:DFN8_2X3MM")
      (libsource (lib "eagle-import") (part "MCP1755_DFN"))
    )
    (comp (ref "U13")
      (value "ADP7142_WSON")
      (footprint "eagle-import:WSON6")
      (libsource (lib "eagle-import") (part "ADP7142_WSON"))
    )
    (comp (ref "U14")
      (value "ADP7182_WSON")
      (footprint "eagle-import:WSON6")
      (libsource (lib "eagle-import") (part "ADP7182_WSON"))
    )
    (comp (ref "U15")
      (value "ADP7182_WSON")
      (footprint "eagle-import:WSON6")
      (libsource (lib "eagle-import") (part "ADP7182_WSON"))
    )
    (comp (ref "C85")
      (value "0.1u")
      (footprint "eagle-import:0402-CAP")
      (libsource (lib "eagle-import") (part "CAP0402-CAP"))
    )
    (comp (ref "C86")
      (value "27p")
      (footprint "eagle-import:0402-CAP")
      (libsource (lib "eagle-import") (part "CAP0402-CAP"))
    )
    (comp (ref "C87")
      (value "27p")
      (footprint "eagle-import:0402-CAP")
      (libsource (lib "eagle-import") (part "CAP0402-CAP"))
    )
    (comp (ref "J3")
      (value "M03X1_0.050_SMD_NO_CREAM")
      (footprint "eagle-import:M03X1_0.050_SMD_NO_CREAM")
      (libsource (lib "eagle-import") (part "M03X1_0.050_SMD_NO_CREAM"))
    )
    (comp (ref "J4")
      (value "USB-MICRO")
      (footprint "eagle-import:USB-MICRO")
      (libsource (lib "eagle-import") (part "USB-MICRO"))
    )
    (comp (ref "J5")
      (value "M20X2_HARFLEX_M")
      (footprint "eagle-import:M20X2_HARFLEX_M")
      (libsource (lib "eagle-import") (part "M20X2_HARFLEX_M"))
    )
    (comp (ref "LED1")
      (value "LED0603")
      (footprint "eagle-import:LED-0603")
      (libsource (lib "eagle-import") (part "LED0603"))
    )
    (comp (ref "R57")
      (value "1.2k")
      (footprint "eagle-import:0402-RES")
      (libsource (lib "eagle-import") (part "RESISTOR0402-RES"))
    )
    (comp (ref "R58")
      (value "100k")
      (footprint "eagle-import:0402-RES")
      (libsource (lib "eagle-import") (part "RESISTOR0402-RES"))
    )
    (comp (ref "R59")
      (value "100k")
      (footprint "eagle-import:0402-RES")
      (libsource (lib "eagle-import") (part "RESISTOR0402-RES"))
    )
    (comp (ref "R60")
      (value "27")
      (footprint "eagle-import:0402-RES")
      (libsource (lib "eagle-import") (part "RESISTOR0402-RES"))
    )
    (comp (ref "R61")
      (value "27")
      (footprint "eagle-import:0402-RES")
      (libsource (lib "eagle-import") (part "RESISTOR0402-RES"))
    )
    (comp (ref "R62")
      (value "1.2k")
      (footprint "eagle-import:0402-RES")
      (libsource (lib "eagle-import") (part "RESISTOR0402-RES"))
    )
    (comp (ref "R63")
      (value "DNP")
      (footprint "eagle-import:0402-RES")
      (libsource (lib "eagle-import") (part "RESISTOR0402-RES"))
    )
    (comp (ref "R64")
      (value "1.2k")
      (footprint "eagle-import:0402-RES")
      (libsource (lib "eagle-import") (part "RESISTOR0402-RES"))
    )
    (comp (ref "S1")
      (value "SWITCH-MOMENTARY-2SMD-3")
      (footprint "eagle-import:TACTILE_SWITCH_SMD-3")
      (libsource (lib "eagle-import") (part "SWITCH-MOMENTARY-2SMD-3"))
    )
    (comp (ref "U9")
      (value "W25Q_USON")
      (footprint "eagle-import:USON8L-2X3MM")
      (libsource (lib "eagle-import") (part "W25Q_USON"))
    )
    (comp (ref "X1")
      (value "CRYSTAL-3.2-2.5")
      (footprint "eagle-import:CRYSTAL-3.2-2.5")
      (libsource (lib "eagle-import") (part "CRYSTAL-3.2-2.5"))
    )
  )
  (nets
    (net (code "1") (name "A_COMM") (class "Default")
      (node (ref "J1") (pin "33") (pinfunction "33_33") (pintype "passive"))
      (node (ref "R63") (pin "2") (pinfunction "2_2") (pintype "passive"))
    )
    (net (code "2") (name "BOOTSEL") (class "Default")
      (node (ref "J5") (pin "B17") (pinfunction "33_B17") (pintype "passive"))
      (node (ref "R57") (pin "1") (pinfunction "1_1") (pintype "passive"))
      (node (ref "S1") (pin "4") (pinfunction "2_4") (pintype "passive"))
    )
    (net (code "3") (name "DET0") (class "Default")
      (node (ref "J1") (pin "4") (pinfunction "4_4") (pintype "passive"))
      (node (ref "R7") (pin "1") (pinfunction "1_1") (pintype "passive"))
      (node (ref "TP4") (pin "P$1") (pinfunction "P$1_P$1") (pintype "bidirectional"))
    )
    (net (code "4") (name "DET1") (class "Default")
      (node (ref "J1") (pin "8") (pinfunction "8_8") (pintype "passive"))
      (node (ref "R1") (pin "1") (pinfunction "1_1") (pintype "passive"))
      (node (ref "TP1") (pin "P$1") (pinfunction "P$1_P$1") (pintype "bidirectional"))
    )
    (net (code "5") (name "DET2") (class "Default")
      (node (ref "J1") (pin "12") (pinfunction "12_12") (pintype "passive"))
      (node (ref "R29") (pin "1") (pinfunction "1_1") (pintype "passive"))
      (node (ref "TP9") (pin "P$1") (pinfunction "P$1_P$1") (pintype "bidirectional"))
    )
    (net (code "6") (name "DET3") (class "Default")
      (node (ref "J1") (pin "16") (pinfunction "16_16") (pintype "passive"))
      (node (ref "R35") (pin "1") (pinfunction "1_1") (pintype "passive"))
      (node (ref "TP11") (pin "P$1") (pinfunction "P$1_P$1") (pintype "bidirectional"))
    )
    (net (code "7") (name "DET4") (class "Default")
      (node (ref "J1") (pin "20") (pinfunction "20_20") (pintype "passive"))
      (node (ref "R21") (pin "1") (pinfunction "1_1") (pintype "passive"))
      (node (ref "TP7") (pin "P$1") (pinfunction "P$1_P$1") (pintype "bidirectional"))
    )
    (net (code "8") (name "DET5") (class "Default")
      (node (ref "J1") (pin "24") (pinfunction "24_24") (pintype "passive"))
      (node (ref "R15") (pin "1") (pinfunction "1_1") (pintype "passive"))
      (node (ref "TP6") (pin "P$1") (pinfunction "P$1_P$1") (pintype "bidirectional"))
    )
    (net (code "9") (name "DET6") (class "Default")
      (node (ref "J1") (pin "28") (pinfunction "28_28") (pintype "passive"))
      (node (ref "R43") (pin "1") (pinfunction "1_1") (pintype "passive"))
      (node (ref "TP13") (pin "P$1") (pinfunction "P$1_P$1") (pintype "bidirectional"))
    )
    (net (code "10") (name "DET7") (class "Default")
      (node (ref "J1") (pin "32") (pinfunction "32_32") (pintype "passive"))
      (node (ref "R49") (pin "1") (pinfunction "1_1") (pintype "passive"))
      (node (ref "TP15") (pin "P$1") (pinfunction "P$1_P$1") (pintype "bidirectional"))
    )
    (net (code "11") (name "GND") (class "Default")
      (node (ref "C10") (pin "2") (pinfunction "2_2") (pintype "passive"))
      (node (ref "C100") (pin "2") (pinfunction "2_2") (pintype "passive"))
      (node (ref "C101") (pin "2") (pinfunction "2_2") (pintype "passive"))
      (node (ref "C102") (pin "2") (pinfunction "2_2") (pintype "passive"))
      (node (ref "C103") (pin "2") (pinfunction "2_2") (pintype "passive"))
      (node (ref "C104") (pin "2") (pinfunction "2_2") (pintype "passive"))
      (node (ref "C105") (pin "2") (pinfunction "2_2") (pintype "passive"))
      (node (ref "C106") (pin "1") (pinfunction "1_1") (pintype "passive"))
      (node (ref "C107") (pin "1") (pinfunction "1_1") (pintype "passive"))
      (node (ref "C108") (pin "1") (pinfunction "1_1") (pintype "passive"))
      (node (ref "C109") (pin "1") (pinfunction "1_1") (pintype "passive"))
      (node (ref "C111") (pin "2") (pinfunction "2_2") (pintype "passive"))
      (node (ref "C112") (pin "1") (pinfunction "1_1") (pintype "passive"))
      (node (ref "C113") (pin "2") (pinfunction "2_2") (pintype "passive"))
      (node (ref "C12") (pin "2") (pinfunction "2_2") (pintype "passive"))
      (node (ref "C13") (pin "2") (pinfunction "2_2") (pintype "passive"))
      (node (ref "C14") (pin "2") (pinfunction "2_2") (pintype "passive"))
      (node (ref "C15") (pin "1") (pinfunction "1_1") (pintype "passive"))
      (node (ref "C17") (pin "2") (pinfunction "2_2") (pintype "passive"))
      (node (ref "C19") (pin "2") (pinfunction "2_2") (pintype "passive"))
      (node (ref "C2") (pin "1") (pinfunction "1_1") (pintype "passive"))
      (node (ref "C20") (pin "2") (pinfunction "2_2") (pintype "passive"))
      (node (ref "C21") (pin "2") (pinfunction "2_2") (pintype "passive"))
      (node (ref "C23") (pin "1") (pinfunction "1_1") (pintype "passive"))
      (node (ref "C25") (pin "2") (pinfunction "2_2") (pintype "passive"))
      (node (ref "C27") (pin "2") (pinfunction "2_2") (pintype "passive"))
      (node (ref "C28") (pin "2") (pinfunction "2_2") (pintype "passive"))
      (node (ref "C29") (pin "2") (pinfunction "2_2") (pintype "passive"))
      (node (ref "C30") (pin "2") (pinfunction "2_2") (pintype "passive"))
      (node (ref "C31") (pin "2") (pinfunction "2_2") (pintype "passive"))
      (node (ref "C33") (pin "2") (pinfunction "2_2") (pintype "passive"))
      (node (ref "C34") (pin "2") (pinfunction "2_2") (pintype "passive"))
      (node (ref "C35") (pin "2") (pinfunction "2_2") (pintype "passive"))
      (node (ref "C36") (pin "1") (pinfunction "1_1") (pintype "passive"))
      (node (ref "C38") (pin "2") (pinfunction "2_2") (pintype "passive"))
      (node (ref "C4") (pin "2") (pinfunction "2_2") (pintype "passive"))
      (node (ref "C40") (pin "2") (pinfunction "2_2") (pintype "passive"))
      (node (ref "C41") (pin "2") (pinfunction "2_2") (pintype "passive"))
      (node (ref "C42") (pin "2") (pinfunction "2_2") (pintype "passive"))
      (node (ref "C44") (pin "1") (pinfunction "1_1") (pintype "passive"))
      (node (ref "C46") (pin "2") (pinfunction "2_2") (pintype "passive"))
      (node (ref "C48") (pin "2") (pinfunction "2_2") (pintype "passive"))
      (node (ref "C49") (pin "2") (pinfunction "2_2") (pintype "passive"))
      (node (ref "C50") (pin "2") (pinfunction "2_2") (pintype "passive"))
      (node (ref "C51") (pin "2") (pinfunction "2_2") (pintype "passive"))
      (node (ref "C52") (pin "2") (pinfunction "2_2") (pintype "passive"))
      (node (ref "C54") (pin "2") (pinfunction "2_2") (pintype "passive"))
      (node (ref "C55") (pin "2") (pinfunction "2_2") (pintype "passive"))
      (node (ref "C56") (pin "2") (pinfunction "2_2") (pintype "passive"))
      (node (ref "C57") (pin "1") (pinfunction "1_1") (pintype "passive"))
      (node (ref "C59") (pin "2") (pinfunction "2_2") (pintype "passive"))
      (node (ref "C6") (pin "2") (pinfunction "2_2") (pintype "passive"))
      (node (ref "C61") (pin "2") (pinfunction "2_2") (pintype "passive"))
      (node (ref "C62") (pin "2") (pinfunction "2_2") (pintype "passive"))
      (node (ref "C63") (pin "2") (pinfunction "2_2") (pintype "passive"))
      (node (ref "C65") (pin "1") (pinfunction "1_1") (pintype "passive"))
      (node (ref "C67") (pin "2") (pinfunction "2_2") (pintype "passive"))
      (node (ref "C69") (pin "2") (pinfunction "2_2") (pintype "passive"))
      (node (ref "C7") (pin "2") (pinfunction "2_2") (pintype "passive"))
      (node (ref "C70") (pin "2") (pinfunction "2_2") (pintype "passive"))
      (node (ref "C71") (pin "2") (pinfunction "2_2") (pintype "passive"))
      (node (ref "C72") (pin "2") (pinfunction "2_2") (pintype "passive"))
      (node (ref "C73") (pin "2") (pinfunction "2_2") (pintype "passive"))
      (node (ref "C75") (pin "2") (pinfunction "2_2") (pintype "passive"))
      (node (ref "C76") (pin "2") (pinfunction "2_2") (pintype "passive"))
      (node (ref "C77") (pin "2") (pinfunction "2_2") (pintype "passive"))
      (node (ref "C78") (pin "1") (pinfunction "1_1") (pintype "passive"))
      (node (ref "C8") (pin "2") (pinfunction "2_2") (pintype "passive"))
      (node (ref "C80") (pin "2") (pinfunction "2_2") (pintype "passive"))
      (node (ref "C82") (pin "2") (pinfunction "2_2") (pintype "passive"))
      (node (ref "C83") (pin "2") (pinfunction "2_2") (pintype "passive"))
      (node (ref "C84") (pin "2") (pinfunction "2_2") (pintype "passive"))
      (node (ref "C85") (pin "2") (pinfunction "2_2") (pintype "passive"))
      (node (ref "C86") (pin "2") (pinfunction "2_2") (pintype "passive"))
      (node (ref "C87") (pin "2") (pinfunction "2_2") (pintype "passive"))
      (node (ref "C88") (pin "2") (pinfunction "2_2") (pintype "passive"))
      (node (ref "C89") (pin "2") (pinfunction "2_2") (pintype "passive"))
      (node (ref "C9") (pin "2") (pinfunction "2_2") (pintype "passive"))
      (node (ref "C90") (pin "2") (pinfunction "2_2") (pintype "passive"))
      (node (ref "C91") (pin "2") (pinfunction "2_2") (pintype "passive"))
      (node (ref "C92") (pin "2") (pinfunction "2_2") (pintype "passive"))
      (node (ref "C93") (pin "2") (pinfunction "2_2") (pintype "passive"))
      (node (ref "C94") (pin "2") (pinfunction "2_2") (pintype "passive"))
      (node (ref "C95") (pin "2") (pinfunction "2_2") (pintype "passive"))
      (node (ref "C96") (pin "2") (pinfunction "2_2") (pintype "passive"))
      (node (ref "C97") (pin "2") (pinfunction "2_2") (pintype "passive"))
      (node (ref "C98") (pin "2") (pinfunction "2_2") (pintype "passive"))
      (node (ref "C99") (pin "2") (pinfunction "2_2") (pintype "passive"))
      (node (ref "J1") (pin "11") (pinfunction "11_11") (pintype "passive"))
      (node (ref "J1") (pin "15") (pinfunction "15_15") (pintype "passive"))
      (node (ref "J1") (pin "19") (pinfunction "19_19") (pintype "passive"))
      (node (ref "J1") (pin "23") (pinfunction "23_23") (pintype "passive"))
      (node (ref "J1") (pin "27") (pinfunction "27_27") (pintype "passive"))
      (node (ref "J1") (pin "3") (pinfunction "3_3") (pintype "passive"))
      (node (ref "J1") (pin "31") (pinfunction "31_31") (pintype "passive"))
      (node (ref "J1") (pin "7") (pinfunction "7_7") (pintype "passive"))
      (node (ref "J2") (pin "1") (pinfunction "1_1") (pintype "passive"))
      (node (ref "J2") (pin "3") (pinfunction "3_3") (pintype "passive"))
      (node (ref "J2") (pin "5") (pinfunction "5_5") (pintype "passive"))
      (node (ref "J2") (pin "7") (pinfunction "7_7") (pintype "passive"))
      (node (ref "J2") (pin "9") (pinfunction "9_9") (pintype "passive"))
      (node (ref "J3") (pin "2") (pinfunction "2_2") (pintype "passive"))
      (node (ref "J4") (pin "5") (pinfunction "5_5") (pintype "bidirectional"))
      (node (ref "J4") (pin "SH1") (pinfunction "SH1_SH1") (pintype "bidirectional"))
      (node (ref "J4") (pin "SH2") (pinfunction "SH2_SH2") (pintype "bidirectional"))
      (node (ref "J4") (pin "SH3") (pinfunction "SH3_SH3") (pintype "bidirectional"))
      (node (ref "J4") (pin "SH4") (pinfunction "SH4_SH4") (pintype "bidirectional"))
      (node (ref "J4") (pin "SH5") (pinfunction "SH5_SH5") (pintype "bidirectional"))
      (node (ref "J4") (pin "SH6") (pinfunction "SH6_SH6") (pintype "bidirectional"))
      (node (ref "J5") (pin "A10") (pinfunction "20_A10") (pintype "passive"))
      (node (ref "J5") (pin "A11") (pinfunction "22_A11") (pintype "passive"))
      (node (ref "J5") (pin "A12") (pinfunction "24_A12") (pintype "passive"))
      (node (ref "J5") (pin "A13") (pinfunction "26_A13") (pintype "passive"))
      (node (ref "J5") (pin "A14") (pinfunction "28_A14") (pintype "passive"))
      (node (ref "J5") (pin "A15") (pinfunction "30_A15") (pintype "passive"))
      (node (ref "J5") (pin "A16") (pinfunction "32_A16") (pintype "passive"))
      (node (ref "J5") (pin "A17") (pinfunction "34_A17") (pintype "passive"))
      (node (ref "J5") (pin "A2") (pinfunction "4_A2") (pintype "passive"))
      (node (ref "J5") (pin "A20") (pinfunction "40_A20") (pintype "passive"))
      (node (ref "J5") (pin "A4") (pinfunction "8_A4") (pintype "passive"))
      (node (ref "J5") (pin "A5") (pinfunction "10_A5") (pintype "passive"))
      (node (ref "J5") (pin "A6") (pinfunction "12_A6") (pintype "passive"))
      (node (ref "J5") (pin "A7") (pinfunction "14_A7") (pintype "passive"))
      (node (ref "J5") (pin "A8") (pinfunction "16_A8") (pintype "passive"))
      (node (ref "J5") (pin "A9") (pinfunction "18_A9") (pintype "passive"))
      (node (ref "J5") (pin "B18") (pinfunction "35_B18") (pintype "passive"))
      (node (ref "J5") (pin "B19") (pinfunction "37_B19") (pintype "passive"))
      (node (ref "J5") (pin "B2") (pinfunction "3_B2") (pintype "passive"))
      (node (ref "J5") (pin "B4") (pinfunction "7_B4") (pintype "passive"))
      (node (ref "J5") (pin "B8") (pinfunction "15_B8") (pintype "passive"))
      (node (ref "LED1") (pin "C") (pinfunction "C_C") (pintype "passive"))
      (node (ref "R10") (pin "1") (pinfunction "1_1") (pintype "passive"))
      (node (ref "R14") (pin "1") (pinfunction "1_1") (pintype "passive"))
      (node (ref "R18") (pin "1") (pinfunction "1_1") (pintype "passive"))
      (node (ref "R24") (pin "1") (pinfunction "1_1") (pintype "passive"))
      (node (ref "R28") (pin "1") (pinfunction "1_1") (pintype "passive"))
      (node (ref "R32") (pin "1") (pinfunction "1_1") (pintype "passive"))
      (node (ref "R38") (pin "1") (pinfunction "1_1") (pintype "passive"))
      (node (ref "R4") (pin "1") (pinfunction "1_1") (pintype "passive"))
      (node (ref "R42") (pin "1") (pinfunction "1_1") (pintype "passive"))
      (node (ref "R46") (pin "1") (pinfunction "1_1") (pintype "passive"))
      (node (ref "R52") (pin "1") (pinfunction "1_1") (pintype "passive"))
      (node (ref "R56") (pin "1") (pinfunction "1_1") (pintype "passive"))
      (node (ref "R67") (pin "1") (pinfunction "1_1") (pintype "passive"))
      (node (ref "R68") (pin "2") (pinfunction "2_2") (pintype "passive"))
      (node (ref "S1") (pin "1") (pinfunction "1_1") (pintype "passive"))
      (node (ref "TP20") (pin "1") (pinfunction "P$1_1") (pintype "bidirectional"))
      (node (ref "U1") (pin "1") (pinfunction "GND_1") (pintype "power_in"))
      (node (ref "U1") (pin "10") (pinfunction "GND_10") (pintype "power_in"))
      (node (ref "U1") (pin "EP") (pinfunction "GND_EP") (pintype "power_in"))
      (node (ref "U10") (pin "19") (pinfunction "TESTEN_19") (pintype "input"))
      (node (ref "U10") (pin "PAD") (pinfunction "GND_PAD") (pintype "power_in"))
      (node (ref "U11") (pin "4") (pinfunction "GND_4") (pintype "power_in"))
      (node (ref "U11") (pin "P") (pinfunction "GND_P") (pintype "power_in"))
      (node (ref "U12") (pin "4") (pinfunction "GND_4") (pintype "power_in"))
      (node (ref "U12") (pin "P") (pinfunction "GND_P") (pintype "power_in"))
      (node (ref "U13") (pin "3") (pinfunction "GND_3") (pintype "power_in"))
      (node (ref "U13") (pin "PAD") (pinfunction "GND_PAD") (pintype "power_in"))
      (node (ref "U14") (pin "5") (pinfunction "GND_5") (pintype "bidirectional"))
      (node (ref "U15") (pin "5") (pinfunction "GND_5") (pintype "bidirectional"))
      (node (ref "U2") (pin "EP") (pinfunction "1_EP") (pintype "passive"))
      (node (ref "U3") (pin "1") (pinfunction "GND_1") (pintype "power_in"))
      (node (ref "U3") (pin "10") (pinfunction "GND_10") (pintype "power_in"))
      (node (ref "U3") (pin "EP") (pinfunction "GND_EP") (pintype "power_in"))
      (node (ref "U4") (pin "EP") (pinfunction "1_EP") (pintype "passive"))
      (node (ref "U5") (pin "1") (pinfunction "GND_1") (pintype "power_in"))
      (node (ref "U5") (pin "10") (pinfunction "GND_10") (pintype "power_in"))
      (node (ref "U5") (pin "EP") (pinfunction "GND_EP") (pintype "power_in"))
      (node (ref "U6") (pin "EP") (pinfunction "1_EP") (pintype "passive"))
      (node (ref "U7") (pin "1") (pinfunction "GND_1") (pintype "power_in"))
      (node (ref "U7") (pin "10") (pinfunction "GND_10") (pintype "power_in"))
      (node (ref "U7") (pin "EP") (pinfunction "GND_EP") (pintype "power_in"))
      (node (ref "U8") (pin "EP") (pinfunction "1_EP") (pintype "passive"))
      (node (ref "U9") (pin "4") (pinfunction "GND_4") (pintype "power_in"))
      (node (ref "X1") (pin "2") (pinfunction "GND_2") (pintype "passive"))
      (node (ref "X1") (pin "4") (pinfunction "GND_4") (pintype "passive"))
    )
    (net (code "12") (name "GPIO00") (class "Default")
      (node (ref "J5") (pin "B15") (pinfunction "29_B15") (pintype "passive"))
      (node (ref "U10") (pin "2") (pinfunction "GPIO00_2") (pintype "bidirectional"))
    )
    (net (code "13") (name "GPIO01") (class "Default")
      (node (ref "J5") (pin "B14") (pinfunction "27_B14") (pintype "passive"))
      (node (ref "U10") (pin "3") (pinfunction "GPIO01_3") (pintype "bidirectional"))
    )
    (net (code "14") (name "GPIO02") (class "Default")
      (node (ref "J5") (pin "B13") (pinfunction "25_B13") (pintype "passive"))
      (node (ref "U10") (pin "4") (pinfunction "GPIO02_4") (pintype "bidirectional"))
    )
    (net (code "15") (name "GPIO03") (class "Default")
      (node (ref "J5") (pin "B12") (pinfunction "23_B12") (pintype "passive"))
      (node (ref "U10") (pin "5") (pinfunction "GPIO03_5") (pintype "bidirectional"))
    )
    (net (code "16") (name "GPIO04") (class "Default")
      (node (ref "J5") (pin "B11") (pinfunction "21_B11") (pintype "passive"))
      (node (ref "U10") (pin "6") (pinfunction "GPIO04_6") (pintype "bidirectional"))
    )
    (net (code "17") (name "GPIO05") (class "Default")
      (node (ref "J5") (pin "B10") (pinfunction "19_B10") (pintype "passive"))
      (node (ref "U10") (pin "7") (pinfunction "GPIO05_7") (pintype "bidirectional"))
    )
    (net (code "18") (name "GPIO06") (class "Default")
      (node (ref "J5") (pin "B9") (pinfunction "17_B9") (pintype "passive"))
      (node (ref "U10") (pin "8") (pinfunction "GPIO06_8") (pintype "bidirectional"))
    )
    (net (code "19") (name "LED") (class "Default")
      (node (ref "R62") (pin "2") (pinfunction "2_2") (pintype "passive"))
      (node (ref "R63") (pin "1") (pinfunction "1_1") (pintype "passive"))
      (node (ref "U10") (pin "9") (pinfunction "GPIO07_9") (pintype "bidirectional"))
    )
    (net (code "20") (name "Net-(C110-Pad1)") (class "Default")
      (node (ref "C110") (pin "1") (pinfunction "1_1") (pintype "passive"))
      (node (ref "R70") (pin "1") (pinfunction "1_1") (pintype "passive"))
    )
    (net (code "21") (name "Net-(J4-Pad2)") (class "Default")
      (node (ref "J4") (pin "2") (pinfunction "2_2") (pintype "bidirectional"))
      (node (ref "R61") (pin "2") (pinfunction "2_2") (pintype "passive"))
    )
    (net (code "22") (name "Net-(J4-Pad3)") (class "Default")
      (node (ref "J4") (pin "3") (pinfunction "3_3") (pintype "bidirectional"))
      (node (ref "R60") (pin "2") (pinfunction "2_2") (pintype "passive"))
    )
    (net (code "23") (name "Net-(LED1-PadA)") (class "Default")
      (node (ref "LED1") (pin "A") (pinfunction "A_A") (pintype "passive"))
      (node (ref "R62") (pin "1") (pinfunction "1_1") (pintype "passive"))
    )
    (net (code "24") (name "Net-(LF1-P$1)") (class "Default")
      (node (ref "J1") (pin "1") (pinfunction "1_1") (pintype "passive"))
      (node (ref "J1") (pin "13") (pinfunction "13_13") (pintype "passive"))
      (node (ref "J1") (pin "17") (pinfunction "17_17") (pintype "passive"))
      (node (ref "J1") (pin "21") (pinfunction "21_21") (pintype "passive"))
      (node (ref "J1") (pin "25") (pinfunction "25_25") (pintype "passive"))
      (node (ref "J1") (pin "29") (pinfunction "29_29") (pintype "passive"))
      (node (ref "J1") (pin "5") (pinfunction "5_5") (pintype "passive"))
      (node (ref "J1") (pin "9") (pinfunction "9_9") (pintype "passive"))
      (node (ref "LF1") (pin "1") (pinfunction "P$1_1") (pintype "bidirectional"))
      (node (ref "TP2") (pin "P$1") (pinfunction "P$1_P$1") (pintype "bidirectional"))
    )
    (net (code "25") (name "Net-(LF2-P$1)") (class "Default")
      (node (ref "J1") (pin "10") (pinfunction "10_10") (pintype "passive"))
      (node (ref "J1") (pin "14") (pinfunction "14_14") (pintype "passive"))
      (node (ref "J1") (pin "18") (pinfunction "18_18") (pintype "passive"))
      (node (ref "J1") (pin "2") (pinfunction "2_2") (pintype "passive"))
      (node (ref "J1") (pin "22") (pinfunction "22_22") (pintype "passive"))
      (node (ref "J1") (pin "26") (pinfunction "26_26") (pintype "passive"))
      (node (ref "J1") (pin "30") (pinfunction "30_30") (pintype "passive"))
      (node (ref "J1") (pin "6") (pinfunction "6_6") (pintype "passive"))
      (node (ref "LF2") (pin "1") (pinfunction "P$1_1") (pintype "bidirectional"))
      (node (ref "TP3") (pin "P$1") (pinfunction "P$1_P$1") (pintype "bidirectional"))
    )
    (net (code "26") (name "Net-(U1-AINA+)") (class "Default")
      (node (ref "C3") (pin "2") (pinfunction "2_2") (pintype "passive"))
      (node (ref "C4") (pin "1") (pinfunction "1_1") (pintype "passive"))
      (node (ref "R6") (pin "2") (pinfunction "2_2") (pintype "passive"))
      (node (ref "U1") (pin "8") (pinfunction "AINA+_8") (pintype "input"))
    )
    (net (code "27") (name "Net-(U1-AINA-)") (class "Default")
      (node (ref "C2") (pin "2") (pinfunction "2_2") (pintype "passive"))
      (node (ref "C3") (pin "1") (pinfunction "1_1") (pintype "passive"))
      (node (ref "R3") (pin "2") (pinfunction "2_2") (pintype "passive"))
      (node (ref "U1") (pin "7") (pinfunction "AINA-_7") (pintype "input"))
    )
    (net (code "28") (name "Net-(U1-AINB+)") (class "Default")
      (node (ref "C16") (pin "2") (pinfunction "2_2") (pintype "passive"))
      (node (ref "C17") (pin "1") (pinfunction "1_1") (pintype "passive"))
      (node (ref "R12") (pin "2") (pinfunction "2_2") (pintype "passive"))
      (node (ref "U1") (pin "6") (pinfunction "AINB+_6") (pintype "input"))
    )
    (net (code "29") (name "Net-(U1-AINB-)") (class "Default")
      (node (ref "C15") (pin "2") (pinfunction "2_2") (pintype "passive"))
      (node (ref "C16") (pin "1") (pinfunction "1_1") (pintype "passive"))
      (node (ref "R9") (pin "2") (pinfunction "2_2") (pintype "passive"))
      (node (ref "U1") (pin "5") (pinfunction "AINB-_5") (pintype "input"))
    )
    (net (code "30") (name "Net-(U1-REFCAP)") (class "Default")
      (node (ref "C13") (pin "1") (pinfunction "1_1") (pintype "passive"))
      (node (ref "U1") (pin "9") (pinfunction "REFCAP_9") (pintype "bidirectional"))
    )
    (net (code "31") (name "Net-(U1-REFIO)") (class "Default")
      (node (ref "C12") (pin "1") (pinfunction "1_1") (pintype "passive"))
      (node (ref "R13") (pin "2") (pinfunction "2_2") (pintype "passive"))
      (node (ref "U1") (pin "11") (pinfunction "REFIO_11") (pintype "bidirectional"))
    )
    (net (code "32") (name "Net-(U1-REGCAP)") (class "Default")
      (node (ref "C14") (pin "1") (pinfunction "1_1") (pintype "passive"))
      (node (ref "U1") (pin "3") (pinfunction "REGCAP_3") (pintype "bidirectional"))
    )
    (net (code "33") (name "Net-(U2A-+FB)") (class "Default")
      (node (ref "C18") (pin "2") (pinfunction "2_2") (pintype "passive"))
      (node (ref "R11") (pin "2") (pinfunction "2_2") (pintype "passive"))
      (node (ref "U2") (pin "2") (pinfunction "+FB_2") (pintype "output"))
    )
    (net (code "34") (name "Net-(U2A-+IN)") (class "Default")
      (node (ref "C11") (pin "1") (pinfunction "1_1") (pintype "passive"))
      (node (ref "R7") (pin "2") (pinfunction "2_2") (pintype "passive"))
      (node (ref "R8") (pin "1") (pinfunction "1_1") (pintype "passive"))
      (node (ref "U2") (pin "24") (pinfunction "+IN_24") (pintype "input"))
    )
    (net (code "35") (name "Net-(U2A-+OUT)") (class "Default")
      (node (ref "R12") (pin "1") (pinfunction "1_1") (pintype "passive"))
      (node (ref "U2") (pin "18") (pinfunction "+OUT_18") (pintype "output"))
    )
    (net (code "36") (name "Net-(U2A--FB)") (class "Default")
      (node (ref "C11") (pin "2") (pinfunction "2_2") (pintype "passive"))
      (node (ref "R8") (pin "2") (pinfunction "2_2") (pintype "passive"))
      (node (ref "U2") (pin "23") (pinfunction "-FB_23") (pintype "output"))
    )
    (net (code "37") (name "Net-(U2A--IN)") (class "Default")
      (node (ref "C18") (pin "1") (pinfunction "1_1") (pintype "passive"))
      (node (ref "R10") (pin "2") (pinfunction "2_2") (pintype "passive"))
      (node (ref "R11") (pin "1") (pinfunction "1_1") (pintype "passive"))
      (node (ref "U2") (pin "1") (pinfunction "-IN_1") (pintype "input"))
    )
    (net (code "38") (name "Net-(U2A--OUT)") (class "Default")
      (node (ref "R9") (pin "1") (pinfunction "1_1") (pintype "passive"))
      (node (ref "U2") (pin "19") (pinfunction "-OUT_19") (pintype "output"))
    )
    (net (code "39") (name "Net-(U2B-+FB)") (class "Default")
      (node (ref "C5") (pin "2") (pinfunction "2_2") (pintype "passive"))
      (node (ref "R5") (pin "2") (pinfunction "2_2") (pintype "passive"))
      (node (ref "U2") (pin "8") (pinfunction "+FB_8") (pintype "output"))
    )
    (net (code "40") (name "Net-(U2B-+IN)") (class "Default")
      (node (ref "C1") (pin "1") (pinfunction "1_1") (pintype "passive"))
      (node (ref "R1") (pin "2") (pinfunction "2_2") (pintype "passive"))
      (node (ref "R2") (pin "1") (pinfunction "1_1") (pintype "passive"))
      (node (ref "U2") (pin "6") (pinfunction "+IN_6") (pintype "input"))
    )
    (net (code "41") (name "Net-(U2B-+OUT)") (class "Default")
      (node (ref "R6") (pin "1") (pinfunction "1_1") (pintype "passive"))
      (node (ref "U2") (pin "12") (pinfunction "+OUT_12") (pintype "output"))
    )
    (net (code "42") (name "Net-(U2B--FB)") (class "Default")
      (node (ref "C1") (pin "2") (pinfunction "2_2") (pintype "passive"))
      (node (ref "R2") (pin "2") (pinfunction "2_2") (pintype "passive"))
      (node (ref "U2") (pin "5") (pinfunction "-FB_5") (pintype "output"))
    )
    (net (code "43") (name "Net-(U2B--IN)") (class "Default")
      (node (ref "C5") (pin "1") (pinfunction "1_1") (pintype "passive"))
      (node (ref "R4") (pin "2") (pinfunction "2_2") (pintype "passive"))
      (node (ref "R5") (pin "1") (pinfunction "1_1") (pintype "passive"))
      (node (ref "U2") (pin "7") (pinfunction "-IN_7") (pintype "input"))
    )
    (net (code "44") (name "Net-(U2B--OUT)") (class "Default")
      (node (ref "R3") (pin "1") (pinfunction "1_1") (pintype "passive"))
      (node (ref "U2") (pin "13") (pinfunction "-OUT_13") (pintype "output"))
    )
    (net (code "45") (name "Net-(U3-AINA+)") (class "Default")
      (node (ref "C24") (pin "2") (pinfunction "2_2") (pintype "passive"))
      (node (ref "C25") (pin "1") (pinfunction "1_1") (pintype "passive"))
      (node (ref "R20") (pin "2") (pinfunction "2_2") (pintype "passive"))
      (node (ref "U3") (pin "8") (pinfunction "AINA+_8") (pintype "input"))
    )
    (net (code "46") (name "Net-(U3-AINA-)") (class "Default")
      (node (ref "C23") (pin "2") (pinfunction "2_2") (pintype "passive"))
      (node (ref "C24") (pin "1") (pinfunction "1_1") (pintype "passive"))
      (node (ref "R17") (pin "2") (pinfunction "2_2") (pintype "passive"))
      (node (ref "U3") (pin "7") (pinfunction "AINA-_7") (pintype "input"))
    )
    (net (code "47") (name "Net-(U3-AINB+)") (class "Default")
      (node (ref "C37") (pin "2") (pinfunction "2_2") (pintype "passive"))
      (node (ref "C38") (pin "1") (pinfunction "1_1") (pintype "passive"))
      (node (ref "R26") (pin "2") (pinfunction "2_2") (pintype "passive"))
      (node (ref "U3") (pin "6") (pinfunction "AINB+_6") (pintype "input"))
    )
    (net (code "48") (name "Net-(U3-AINB-)") (class "Default")
      (node (ref "C36") (pin "2") (pinfunction "2_2") (pintype "passive"))
      (node (ref "C37") (pin "1") (pinfunction "1_1") (pintype "passive"))
      (node (ref "R23") (pin "2") (pinfunction "2_2") (pintype "passive"))
      (node (ref "U3") (pin "5") (pinfunction "AINB-_5") (pintype "input"))
    )
    (net (code "49") (name "Net-(U3-REFCAP)") (class "Default")
      (node (ref "C34") (pin "1") (pinfunction "1_1") (pintype "passive"))
      (node (ref "U3") (pin "9") (pinfunction "REFCAP_9") (pintype "bidirectional"))
    )
    (net (code "50") (name "Net-(U3-REFIO)") (class "Default")
      (node (ref "C33") (pin "1") (pinfunction "1_1") (pintype "passive"))
      (node (ref "R27") (pin "2") (pinfunction "2_2") (pintype "passive"))
      (node (ref "U3") (pin "11") (pinfunction "REFIO_11") (pintype "bidirectional"))
    )
    (net (code "51") (name "Net-(U3-REGCAP)") (class "Default")
      (node (ref "C35") (pin "1") (pinfunction "1_1") (pintype "passive"))
      (node (ref "U3") (pin "3") (pinfunction "REGCAP_3") (pintype "bidirectional"))
    )
    (net (code "52") (name "Net-(U4A-+FB)") (class "Default")
      (node (ref "C39") (pin "2") (pinfunction "2_2") (pintype "passive"))
      (node (ref "R25") (pin "2") (pinfunction "2_2") (pintype "passive"))
      (node (ref "U4") (pin "2") (pinfunction "+FB_2") (pintype "output"))
    )
    (net (code "53") (name "Net-(U4A-+IN)") (class "Default")
      (node (ref "C32") (pin "1") (pinfunction "1_1") (pintype "passive"))
      (node (ref "R21") (pin "2") (pinfunction "2_2") (pintype "passive"))
      (node (ref "R22") (pin "1") (pinfunction "1_1") (pintype "passive"))
      (node (ref "U4") (pin "24") (pinfunction "+IN_24") (pintype "input"))
    )
    (net (code "54") (name "Net-(U4A-+OUT)") (class "Default")
      (node (ref "R26") (pin "1") (pinfunction "1_1") (pintype "passive"))
      (node (ref "U4") (pin "18") (pinfunction "+OUT_18") (pintype "output"))
    )
    (net (code "55") (name "Net-(U4A--FB)") (class "Default")
      (node (ref "C32") (pin "2") (pinfunction "2_2") (pintype "passive"))
      (node (ref "R22") (pin "2") (pinfunction "2_2") (pintype "passive"))
      (node (ref "U4") (pin "23") (pinfunction "-FB_23") (pintype "output"))
    )
    (net (code "56") (name "Net-(U4A--IN)") (class "Default")
      (node (ref "C39") (pin "1") (pinfunction "1_1") (pintype "passive"))
      (node (ref "R24") (pin "2") (pinfunction "2_2") (pintype "passive"))
      (node (ref "R25") (pin "1") (pinfunction "1_1") (pintype "passive"))
      (node (ref "U4") (pin "1") (pinfunction "-IN_1") (pintype "input"))
    )
    (net (code "57") (name "Net-(U4A--OUT)") (class "Default")
      (node (ref "R23") (pin "1") (pinfunction "1_1") (pintype "passive"))
      (node (ref "U4") (pin "19") (pinfunction "-OUT_19") (pintype "output"))
    )
    (net (code "58") (name "Net-(U4B-+FB)") (class "Default")
      (node (ref "C26") (pin "2") (pinfunction "2_2") (pintype "passive"))
      (node (ref "R19") (pin "2") (pinfunction "2_2") (pintype "passive"))
      (node (ref "U4") (pin "8") (pinfunction "+FB_8") (pintype "output"))
    )
    (net (code "59") (name "Net-(U4B-+IN)") (class "Default")
      (node (ref "C22") (pin "1") (pinfunction "1_1") (pintype "passive"))
      (node (ref "R15") (pin "2") (pinfunction "2_2") (pintype "passive"))
      (node (ref "R16") (pin "1") (pinfunction "1_1") (pintype "passive"))
      (node (ref "U4") (pin "6") (pinfunction "+IN_6") (pintype "input"))
    )
    (net (code "60") (name "Net-(U4B-+OUT)") (class "Default")
      (node (ref "R20") (pin "1") (pinfunction "1_1") (pintype "passive"))
      (node (ref "U4") (pin "12") (pinfunction "+OUT_12") (pintype "output"))
    )
    (net (code "61") (name "Net-(U4B--FB)") (class "Default")
      (node (ref "C22") (pin "2") (pinfunction "2_2") (pintype "passive"))
      (node (ref "R16") (pin "2") (pinfunction "2_2") (pintype "passive"))
      (node (ref "U4") (pin "5") (pinfunction "-FB_5") (pintype "output"))
    )
    (net (code "62") (name "Net-(U4B--IN)") (class "Default")
      (node (ref "C26") (pin "1") (pinfunction "1_1") (pintype "passive"))
      (node (ref "R18") (pin "2") (pinfunction "2_2") (pintype "passive"))
      (node (ref "R19") (pin "1") (pinfunction "1_1") (pintype "passive"))
      (node (ref "U4") (pin "7") (pinfunction "-IN_7") (pintype "input"))
    )
    (net (code "63") (name "Net-(U4B--OUT)") (class "Default")
      (node (ref "R17") (pin "1") (pinfunction "1_1") (pintype "passive"))
      (node (ref "U4") (pin "13") (pinfunction "-OUT_13") (pintype "output"))
    )
    (net (code "64") (name "Net-(U5-AINA+)") (class "Default")
      (node (ref "C45") (pin "2") (pinfunction "2_2") (pintype "passive"))
      (node (ref "C46") (pin "1") (pinfunction "1_1") (pintype "passive"))
      (node (ref "R34") (pin "2") (pinfunction "2_2") (pintype "passive"))
      (node (ref "U5") (pin "8") (pinfunction "AINA+_8") (pintype "input"))
    )
    (net (code "65") (name "Net-(U5-AINA-)") (class "Default")
      (node (ref "C44") (pin "2") (pinfunction "2_2") (pintype "passive"))
      (node (ref "C45") (pin "1") (pinfunction "1_1") (pintype "passive"))
      (node (ref "R31") (pin "2") (pinfunction "2_2") (pintype "passive"))
      (node (ref "U5") (pin "7") (pinfunction "AINA-_7") (pintype "input"))
    )
    (net (code "66") (name "Net-(U5-AINB+)") (class "Default")
      (node (ref "C58") (pin "2") (pinfunction "2_2") (pintype "passive"))
      (node (ref "C59") (pin "1") (pinfunction "1_1") (pintype "passive"))
      (node (ref "R40") (pin "2") (pinfunction "2_2") (pintype "passive"))
      (node (ref "U5") (pin "6") (pinfunction "AINB+_6") (pintype "input"))
    )
    (net (code "67") (name "Net-(U5-AINB-)") (class "Default")
      (node (ref "C57") (pin "2") (pinfunction "2_2") (pintype "passive"))
      (node (ref "C58") (pin "1") (pinfunction "1_1") (pintype "passive"))
      (node (ref "R37") (pin "2") (pinfunction "2_2") (pintype "passive"))
      (node (ref "U5") (pin "5") (pinfunction "AINB-_5") (pintype "input"))
    )
    (net (code "68") (name "Net-(U5-REFCAP)") (class "Default")
      (node (ref "C55") (pin "1") (pinfunction "1_1") (pintype "passive"))
      (node (ref "U5") (pin "9") (pinfunction "REFCAP_9") (pintype "bidirectional"))
    )
    (net (code "69") (name "Net-(U5-REFIO)") (class "Default")
      (node (ref "C54") (pin "1") (pinfunction "1_1") (pintype "passive"))
      (node (ref "R41") (pin "2") (pinfunction "2_2") (pintype "passive"))
      (node (ref "U5") (pin "11") (pinfunction "REFIO_11") (pintype "bidirectional"))
    )
    (net (code "70") (name "Net-(U5-REGCAP)") (class "Default")
      (node (ref "C56") (pin "1") (pinfunction "1_1") (pintype "passive"))
      (node (ref "U5") (pin "3") (pinfunction "REGCAP_3") (pintype "bidirectional"))
    )
    (net (code "71") (name "Net-(U6A-+FB)") (class "Default")
      (node (ref "C60") (pin "2") (pinfunction "2_2") (pintype "passive"))
      (node (ref "R39") (pin "2") (pinfunction "2_2") (pintype "passive"))
      (node (ref "U6") (pin "2") (pinfunction "+FB_2") (pintype "output"))
    )
    (net (code "72") (name "Net-(U6A-+IN)") (class "Default")
      (node (ref "C53") (pin "1") (pinfunction "1_1") (pintype "passive"))
      (node (ref "R35") (pin "2") (pinfunction "2_2") (pintype "passive"))
      (node (ref "R36") (pin "1") (pinfunction "1_1") (pintype "passive"))
      (node (ref "U6") (pin "24") (pinfunction "+IN_24") (pintype "input"))
    )
    (net (code "73") (name "Net-(U6A-+OUT)") (class "Default")
      (node (ref "R40") (pin "1") (pinfunction "1_1") (pintype "passive"))
      (node (ref "U6") (pin "18") (pinfunction "+OUT_18") (pintype "output"))
    )
    (net (code "74") (name "Net-(U6A--FB)") (class "Default")
      (node (ref "C53") (pin "2") (pinfunction "2_2") (pintype "passive"))
      (node (ref "R36") (pin "2") (pinfunction "2_2") (pintype "passive"))
      (node (ref "U6") (pin "23") (pinfunction "-FB_23") (pintype "output"))
    )
    (net (code "75") (name "Net-(U6A--IN)") (class "Default")
      (node (ref "C60") (pin "1") (pinfunction "1_1") (pintype "passive"))
      (node (ref "R38") (pin "2") (pinfunction "2_2") (pintype "passive"))
      (node (ref "R39") (pin "1") (pinfunction "1_1") (pintype "passive"))
      (node (ref "U6") (pin "1") (pinfunction "-IN_1") (pintype "input"))
    )
    (net (code "76") (name "Net-(U6A--OUT)") (class "Default")
      (node (ref "R37") (pin "1") (pinfunction "1_1") (pintype "passive"))
      (node (ref "U6") (pin "19") (pinfunction "-OUT_19") (pintype "output"))
    )
    (net (code "77") (name "Net-(U6B-+FB)") (class "Default")
      (node (ref "C47") (pin "2") (pinfunction "2_2") (pintype "passive"))
      (node (ref "R33") (pin "2") (pinfunction "2_2") (pintype "passive"))
      (node (ref "U6") (pin "8") (pinfunction "+FB_8") (pintype "output"))
    )
    (net (code "78") (name "Net-(U6B-+IN)") (class "Default")
      (node (ref "C43") (pin "1") (pinfunction "1_1") (pintype "passive"))
      (node (ref "R29") (pin "2") (pinfunction "2_2") (pintype "passive"))
      (node (ref "R30") (pin "1") (pinfunction "1_1") (pintype "passive"))
      (node (ref "U6") (pin "6") (pinfunction "+IN_6") (pintype "input"))
    )
    (net (code "79") (name "Net-(U6B-+OUT)") (class "Default")
      (node (ref "R34") (pin "1") (pinfunction "1_1") (pintype "passive"))
      (node (ref "U6") (pin "12") (pinfunction "+OUT_12") (pintype "output"))
    )
    (net (code "80") (name "Net-(U6B--FB)") (class "Default")
      (node (ref "C43") (pin "2") (pinfunction "2_2") (pintype "passive"))
      (node (ref "R30") (pin "2") (pinfunction "2_2") (pintype "passive"))
      (node (ref "U6") (pin "5") (pinfunction "-FB_5") (pintype "output"))
    )
    (net (code "81") (name "Net-(U6B--IN)") (class "Default")
      (node (ref "C47") (pin "1") (pinfunction "1_1") (pintype "passive"))
      (node (ref "R32") (pin "2") (pinfunction "2_2") (pintype "passive"))
      (node (ref "R33") (pin "1") (pinfunction "1_1") (pintype "passive"))
      (node (ref "U6") (pin "7") (pinfunction "-IN_7") (pintype "input"))
    )
    (net (code "82") (name "Net-(U6B--OUT)") (class "Default")
      (node (ref "R31") (pin "1") (pinfunction "1_1") (pintype "passive"))
      (node (ref "U6") (pin "13") (pinfunction "-OUT_13") (pintype "output"))
    )
    (net (code "83") (name "Net-(U7-AINA+)") (class "Default")
      (node (ref "C66") (pin "2") (pinfunction "2_2") (pintype "passive"))
      (node (ref "C67") (pin "1") (pinfunction "1_1") (pintype "passive"))
      (node (ref "R48") (pin "2") (pinfunction "2_2") (pintype "passive"))
      (node (ref "U7") (pin "8") (pinfunction "AINA+_8") (pintype "input"))
    )
    (net (code "84") (name "Net-(U7-AINA-)") (class "Default")
      (node (ref "C65") (pin "2") (pinfunction "2_2") (pintype "passive"))
      (node (ref "C66") (pin "1") (pinfunction "1_1") (pintype "passive"))
      (node (ref "R45") (pin "2") (pinfunction "2_2") (pintype "passive"))
      (node (ref "U7") (pin "7") (pinfunction "AINA-_7") (pintype "input"))
    )
    (net (code "85") (name "Net-(U7-AINB+)") (class "Default")
      (node (ref "C79") (pin "2") (pinfunction "2_2") (pintype "passive"))
      (node (ref "C80") (pin "1") (pinfunction "1_1") (pintype "passive"))
      (node (ref "R54") (pin "2") (pinfunction "2_2") (pintype "passive"))
      (node (ref "U7") (pin "6") (pinfunction "AINB+_6") (pintype "input"))
    )
    (net (code "86") (name "Net-(U7-AINB-)") (class "Default")
      (node (ref "C78") (pin "2") (pinfunction "2_2") (pintype "passive"))
      (node (ref "C79") (pin "1") (pinfunction "1_1") (pintype "passive"))
      (node (ref "R51") (pin "2") (pinfunction "2_2") (pintype "passive"))
      (node (ref "U7") (pin "5") (pinfunction "AINB-_5") (pintype "input"))
    )
    (net (code "87") (name "Net-(U7-REFCAP)") (class "Default")
      (node (ref "C76") (pin "1") (pinfunction "1_1") (pintype "passive"))
      (node (ref "U7") (pin "9") (pinfunction "REFCAP_9") (pintype "bidirectional"))
    )
    (net (code "88") (name "Net-(U7-REFIO)") (class "Default")
      (node (ref "C75") (pin "1") (pinfunction "1_1") (pintype "passive"))
      (node (ref "R55") (pin "2") (pinfunction "2_2") (pintype "passive"))
      (node (ref "U7") (pin "11") (pinfunction "REFIO_11") (pintype "bidirectional"))
    )
    (net (code "89") (name "Net-(U7-REGCAP)") (class "Default")
      (node (ref "C77") (pin "1") (pinfunction "1_1") (pintype "passive"))
      (node (ref "U7") (pin "3") (pinfunction "REGCAP_3") (pintype "bidirectional"))
    )
    (net (code "90") (name "Net-(U8A-+FB)") (class "Default")
      (node (ref "C81") (pin "2") (pinfunction "2_2") (pintype "passive"))
      (node (ref "R53") (pin "2") (pinfunction "2_2") (pintype "passive"))
      (node (ref "U8") (pin "2") (pinfunction "+FB_2") (pintype "output"))
    )
    (net (code "91") (name "Net-(U8A-+IN)") (class "Default")
      (node (ref "C74") (pin "1") (pinfunction "1_1") (pintype "passive"))
      (node (ref "R49") (pin "2") (pinfunction "2_2") (pintype "passive"))
      (node (ref "R50") (pin "1") (pinfunction "1_1") (pintype "passive"))
      (node (ref "U8") (pin "24") (pinfunction "+IN_24") (pintype "input"))
    )
    (net (code "92") (name "Net-(U8A-+OUT)") (class "Default")
      (node (ref "R54") (pin "1") (pinfunction "1_1") (pintype "passive"))
      (node (ref "U8") (pin "18") (pinfunction "+OUT_18") (pintype "output"))
    )
    (net (code "93") (name "Net-(U8A--FB)") (class "Default")
      (node (ref "C74") (pin "2") (pinfunction "2_2") (pintype "passive"))
      (node (ref "R50") (pin "2") (pinfunction "2_2") (pintype "passive"))
      (node (ref "U8") (pin "23") (pinfunction "-FB_23") (pintype "output"))
    )
    (net (code "94") (name "Net-(U8A--IN)") (class "Default")
      (node (ref "C81") (pin "1") (pinfunction "1_1") (pintype "passive"))
      (node (ref "R52") (pin "2") (pinfunction "2_2") (pintype "passive"))
      (node (ref "R53") (pin "1") (pinfunction "1_1") (pintype "passive"))
      (node (ref "U8") (pin "1") (pinfunction "-IN_1") (pintype "input"))
    )
    (net (code "95") (name "Net-(U8A--OUT)") (class "Default")
      (node (ref "R51") (pin "1") (pinfunction "1_1") (pintype "passive"))
      (node (ref "U8") (pin "19") (pinfunction "-OUT_19") (pintype "output"))
    )
    (net (code "96") (name "Net-(U8B-+FB)") (class "Default")
      (node (ref "C68") (pin "2") (pinfunction "2_2") (pintype "passive"))
      (node (ref "R47") (pin "2") (pinfunction "2_2") (pintype "passive"))
      (node (ref "U8") (pin "8") (pinfunction "+FB_8") (pintype "output"))
    )
    (net (code "97") (name "Net-(U8B-+IN)") (class "Default")
      (node (ref "C64") (pin "1") (pinfunction "1_1") (pintype "passive"))
      (node (ref "R43") (pin "2") (pinfunction "2_2") (pintype "passive"))
      (node (ref "R44") (pin "1") (pinfunction "1_1") (pintype "passive"))
      (node (ref "U8") (pin "6") (pinfunction "+IN_6") (pintype "input"))
    )
    (net (code "98") (name "Net-(U8B-+OUT)") (class "Default")
      (node (ref "R48") (pin "1") (pinfunction "1_1") (pintype "passive"))
      (node (ref "U8") (pin "12") (pinfunction "+OUT_12") (pintype "output"))
    )
    (net (code "99") (name "Net-(U8B--FB)") (class "Default")
      (node (ref "C64") (pin "2") (pinfunction "2_2") (pintype "passive"))
      (node (ref "R44") (pin "2") (pinfunction "2_2") (pintype "passive"))
      (node (ref "U8") (pin "5") (pinfunction "-FB_5") (pintype "output"))
    )
    (net (code "100") (name "Net-(U8B--IN)") (class "Default")
      (node (ref "C68") (pin "1") (pinfunction "1_1") (pintype "passive"))
      (node (ref "R46") (pin "2") (pinfunction "2_2") (pintype "passive"))
      (node (ref "R47") (pin "1") (pinfunction "1_1") (pintype "passive"))
      (node (ref "U8") (pin "7") (pinfunction "-IN_7") (pintype "input"))
    )
    (net (code "101") (name "Net-(U8B--OUT)") (class "Default")
      (node (ref "R45") (pin "1") (pinfunction "1_1") (pintype "passive"))
      (node (ref "U8") (pin "13") (pinfunction "-OUT_13") (pintype "output"))
    )
    (net (code "102") (name "Net-(U10B-USB_DN)") (class "Default")
      (node (ref "R61") (pin "1") (pinfunction "1_1") (pintype "passive"))
      (node (ref "U10") (pin "46") (pinfunction "USB_DN_46") (pintype "bidirectional"))
    )
    (net (code "103") (name "Net-(U10B-USB_DP)") (class "Default")
      (node (ref "R60") (pin "1") (pinfunction "1_1") (pintype "passive"))
      (node (ref "U10") (pin "47") (pinfunction "USB_DP_47") (pintype "bidirectional"))
    )
    (net (code "104") (name "Net-(U10B-XIN)") (class "Default")
      (node (ref "C87") (pin "1") (pinfunction "1_1") (pintype "passive"))
      (node (ref "U10") (pin "20") (pinfunction "XIN_20") (pintype "bidirectional"))
      (node (ref "X1") (pin "3") (pinfunction "C2_3") (pintype "passive"))
    )
    (net (code "105") (name "Net-(U10B-XOUT)") (class "Default")
      (node (ref "R64") (pin "1") (pinfunction "1_1") (pintype "passive"))
      (node (ref "U10") (pin "21") (pinfunction "XOUT_21") (pintype "bidirectional"))
    )
    (net (code "106") (name "Net-(U10C-ADC_VDD)") (class "Default")
      (node (ref "C93") (pin "1") (pinfunction "1_1") (pintype "passive"))
      (node (ref "R65") (pin "2") (pinfunction "2_2") (pintype "passive"))
      (node (ref "U10") (pin "43") (pinfunction "ADC_VDD_43") (pintype "power_in"))
    )
    (net (code "107") (name "Net-(U13-SENSE{slash}ADJ)") (class "Default")
      (node (ref "R66") (pin "1") (pinfunction "1_1") (pintype "passive"))
      (node (ref "R67") (pin "2") (pinfunction "2_2") (pintype "passive"))
      (node (ref "U13") (pin "2") (pinfunction "SENSE/ADJ_2") (pintype "input"))
    )
    (net (code "108") (name "Net-(U15-NC{slash}ADJ)") (class "Default")
      (node (ref "R68") (pin "1") (pinfunction "1_1") (pintype "passive"))
      (node (ref "R69") (pin "2") (pinfunction "2_2") (pintype "passive"))
      (node (ref "R70") (pin "2") (pinfunction "2_2") (pintype "passive"))
      (node (ref "U15") (pin "2") (pinfunction "NC/ADJ_2") (pintype "bidirectional"))
    )
    (net (code "109") (name "Net-(X1-C1)") (class "Default")
      (node (ref "C86") (pin "1") (pinfunction "1_1") (pintype "passive"))
      (node (ref "R64") (pin "2") (pinfunction "2_2") (pintype "passive"))
      (node (ref "X1") (pin "1") (pinfunction "C1_1") (pintype "passive"))
    )
    (net (code "110") (name "OPT_EN_VN") (class "Default")
      (node (ref "U10") (pin "12") (pinfunction "GPIO09_12") (pintype "bidirectional"))
      (node (ref "U15") (pin "3") (pinfunction "EN_3") (pintype "bidirectional"))
    )
    (net (code "111") (name "OPT_EN_VP") (class "Default")
      (node (ref "U10") (pin "11") (pinfunction "GPIO08_11") (pintype "bidirectional"))
      (node (ref "U13") (pin "4") (pinfunction "EN_4") (pintype "input"))
    )
    (net (code "112") (name "QSPI_SCLK") (class "Default")
      (node (ref "U10") (pin "52") (pinfunction "QSPI_SCLK_52") (pintype "output"))
      (node (ref "U9") (pin "6") (pinfunction "CLK_6") (pintype "input"))
    )
    (net (code "113") (name "QSPI_SD0") (class "Default")
      (node (ref "U10") (pin "53") (pinfunction "QSPI_SD0_53") (pintype "bidirectional"))
      (node (ref "U9") (pin "5") (pinfunction "DI/IO[0]_5") (pintype "bidirectional"))
    )
    (net (code "114") (name "QSPI_SD1") (class "Default")
      (node (ref "U10") (pin "55") (pinfunction "QSPI_SD1_55") (pintype "bidirectional"))
      (node (ref "U9") (pin "2") (pinfunction "DO/IO[1]_2") (pintype "bidirectional"))
    )
    (net (code "115") (name "QSPI_SD2") (class "Default")
      (node (ref "U10") (pin "54") (pinfunction "QSPI_SD2_54") (pintype "bidirectional"))
      (node (ref "U9") (pin "3") (pinfunction "#WP/IO[2]_3") (pintype "bidirectional"))
    )
    (net (code "116") (name "QSPI_SD3") (class "Default")
      (node (ref "U10") (pin "51") (pinfunction "QSPI_SD3_51") (pintype "bidirectional"))
      (node (ref "U9") (pin "7") (pinfunction "#HOLD/IO[3]_7") (pintype "bidirectional"))
    )
    (net (code "117") (name "QSPI_SS_N") (class "Default")
      (node (ref "R57") (pin "2") (pinfunction "2_2") (pintype "passive"))
      (node (ref "R58") (pin "1") (pinfunction "1_1") (pintype "passive"))
      (node (ref "U10") (pin "56") (pinfunction "QSPI_SS_N_56") (pintype "output"))
      (node (ref "U9") (pin "1") (pinfunction "/CS_1") (pintype "input"))
    )
    (net (code "118") (name "RUN") (class "Default")
      (node (ref "J5") (pin "B7") (pinfunction "13_B7") (pintype "passive"))
      (node (ref "R59") (pin "1") (pinfunction "1_1") (pintype "passive"))
      (node (ref "U10") (pin "26") (pinfunction "RUN_26") (pintype "input"))
    )
    (net (code "119") (name "SCLK_A1") (class "Default")
      (node (ref "U1") (pin "16") (pinfunction "SCLK_16") (pintype "input"))
      (node (ref "U10") (pin "28") (pinfunction "GPIO17_28") (pintype "bidirectional"))
    )
    (net (code "120") (name "SCLK_A2") (class "Default")
      (node (ref "U10") (pin "38") (pinfunction "GPIO26/ADC0_38") (pintype "bidirectional"))
      (node (ref "U3") (pin "16") (pinfunction "SCLK_16") (pintype "input"))
    )
    (net (code "121") (name "SCLK_A3") (class "Default")
      (node (ref "J2") (pin "10") (pinfunction "10_10") (pintype "passive"))
      (node (ref "U10") (pin "16") (pinfunction "GPIO13_16") (pintype "bidirectional"))
      (node (ref "U5") (pin "16") (pinfunction "SCLK_16") (pintype "input"))
    )
    (net (code "122") (name "SCLK_A4") (class "Default")
      (node (ref "U10") (pin "34") (pinfunction "GPIO22_34") (pintype "bidirectional"))
      (node (ref "U7") (pin "16") (pinfunction "SCLK_16") (pintype "input"))
    )
    (net (code "123") (name "SDI_A1") (class "Default")
      (node (ref "U1") (pin "15") (pinfunction "SDI_15") (pintype "input"))
      (node (ref "U10") (pin "29") (pinfunction "GPIO18_29") (pintype "bidirectional"))
    )
    (net (code "124") (name "SDI_A2") (class "Default")
      (node (ref "U10") (pin "39") (pinfunction "GPIO27/ADC1_39") (pintype "bidirectional"))
      (node (ref "U3") (pin "15") (pinfunction "SDI_15") (pintype "input"))
    )
    (net (code "125") (name "SDI_A3") (class "Default")
      (node (ref "J2") (pin "8") (pinfunction "8_8") (pintype "passive"))
      (node (ref "U10") (pin "17") (pinfunction "GPIO14_17") (pintype "bidirectional"))
      (node (ref "U5") (pin "15") (pinfunction "SDI_15") (pintype "input"))
    )
    (net (code "126") (name "SDI_A4") (class "Default")
      (node (ref "U10") (pin "35") (pinfunction "GPIO23_35") (pintype "bidirectional"))
      (node (ref "U7") (pin "15") (pinfunction "SDI_15") (pintype "input"))
    )
    (net (code "127") (name "SDOA_A1") (class "Default")
      (node (ref "U1") (pin "13") (pinfunction "SDOA_13") (pintype "output"))
      (node (ref "U10") (pin "31") (pinfunction "GPIO20_31") (pintype "bidirectional"))
    )
    (net (code "128") (name "SDOA_A2") (class "Default")
      (node (ref "U10") (pin "41") (pinfunction "GPIO29/ADC3_41") (pintype "bidirectional"))
      (node (ref "U3") (pin "13") (pinfunction "SDOA_13") (pintype "output"))
    )
    (net (code "129") (name "SDOA_A3") (class "Default")
      (node (ref "J2") (pin "4") (pinfunction "4_4") (pintype "passive"))
      (node (ref "U10") (pin "18") (pinfunction "GPIO15_18") (pintype "bidirectional"))
      (node (ref "U5") (pin "13") (pinfunction "SDOA_13") (pintype "output"))
    )
    (net (code "130") (name "SDOA_A4") (class "Default")
      (node (ref "U10") (pin "36") (pinfunction "GPIO24_36") (pintype "bidirectional"))
      (node (ref "U7") (pin "13") (pinfunction "SDOA_13") (pintype "output"))
    )
    (net (code "131") (name "SDOB_A1") (class "Default")
      (node (ref "U1") (pin "14") (pinfunction "SDOB_14") (pintype "output"))
      (node (ref "U10") (pin "30") (pinfunction "GPIO19_30") (pintype "bidirectional"))
    )
    (net (code "132") (name "SDOB_A2") (class "Default")
      (node (ref "U10") (pin "40") (pinfunction "GPIO28/ADC2_40") (pintype "bidirectional"))
      (node (ref "U3") (pin "14") (pinfunction "SDOB_14") (pintype "output"))
    )
    (net (code "133") (name "SDOB_A3") (class "Default")
      (node (ref "J2") (pin "6") (pinfunction "6_6") (pintype "passive"))
      (node (ref "U10") (pin "14") (pinfunction "GPIO11_14") (pintype "bidirectional"))
      (node (ref "U5") (pin "14") (pinfunction "SDOB_14") (pintype "output"))
    )
    (net (code "134") (name "SDOB_A4") (class "Default")
      (node (ref "U10") (pin "13") (pinfunction "GPIO10_13") (pintype "bidirectional"))
      (node (ref "U7") (pin "14") (pinfunction "SDOB_14") (pintype "output"))
    )
    (net (code "135") (name "SWCLK") (class "Default")
      (node (ref "J3") (pin "1") (pinfunction "1_1") (pintype "passive"))
      (node (ref "J5") (pin "B6") (pinfunction "11_B6") (pintype "passive"))
      (node (ref "U10") (pin "24") (pinfunction "SWCLK_24") (pintype "input"))
    )
    (net (code "136") (name "SWDIO") (class "Default")
      (node (ref "J3") (pin "3") (pinfunction "3_3") (pintype "passive"))
      (node (ref "J5") (pin "B5") (pinfunction "9_B5") (pintype "passive"))
      (node (ref "U10") (pin "25") (pinfunction "SWDIO_25") (pintype "bidirectional"))
    )
    (net (code "137") (name "V1P1") (class "Default")
      (node (ref "C91") (pin "1") (pinfunction "1_1") (pintype "passive"))
      (node (ref "C96") (pin "1") (pinfunction "1_1") (pintype "passive"))
      (node (ref "C97") (pin "1") (pinfunction "1_1") (pintype "passive"))
      (node (ref "TP21") (pin "P$1") (pinfunction "P$1_P$1") (pintype "bidirectional"))
      (node (ref "U10") (pin "23") (pinfunction "DVDD_23") (pintype "power_in"))
      (node (ref "U10") (pin "45") (pinfunction "VREG_VOUT_45") (pintype "power_in"))
      (node (ref "U10") (pin "50") (pinfunction "DVDD_50") (pintype "power_in"))
    )
    (net (code "138") (name "V3P3") (class "Default")
      (node (ref "C100") (pin "1") (pinfunction "1_1") (pintype "passive"))
      (node (ref "C101") (pin "1") (pinfunction "1_1") (pintype "passive"))
      (node (ref "C102") (pin "1") (pinfunction "1_1") (pintype "passive"))
      (node (ref "C103") (pin "1") (pinfunction "1_1") (pintype "passive"))
      (node (ref "C113") (pin "1") (pinfunction "1_1") (pintype "passive"))
      (node (ref "C28") (pin "1") (pinfunction "1_1") (pintype "passive"))
      (node (ref "C49") (pin "1") (pinfunction "1_1") (pintype "passive"))
      (node (ref "C7") (pin "1") (pinfunction "1_1") (pintype "passive"))
      (node (ref "C70") (pin "1") (pinfunction "1_1") (pintype "passive"))
      (node (ref "C85") (pin "1") (pinfunction "1_1") (pintype "passive"))
      (node (ref "C90") (pin "1") (pinfunction "1_1") (pintype "passive"))
      (node (ref "C92") (pin "1") (pinfunction "1_1") (pintype "passive"))
      (node (ref "C98") (pin "1") (pinfunction "1_1") (pintype "passive"))
      (node (ref "C99") (pin "1") (pinfunction "1_1") (pintype "passive"))
      (node (ref "J5") (pin "B16") (pinfunction "31_B16") (pintype "passive"))
      (node (ref "R58") (pin "2") (pinfunction "2_2") (pintype "passive"))
      (node (ref "R59") (pin "2") (pinfunction "2_2") (pintype "passive"))
      (node (ref "R65") (pin "1") (pinfunction "1_1") (pintype "passive"))
      (node (ref "TP17") (pin "P$1") (pinfunction "P$1_P$1") (pintype "bidirectional"))
      (node (ref "U1") (pin "2") (pinfunction "VLOGIC_2") (pintype "power_in"))
      (node (ref "U10") (pin "1") (pinfunction "IOVDD_1") (pintype "power_in"))
      (node (ref "U10") (pin "10") (pinfunction "IOVDD_10") (pintype "power_in"))
      (node (ref "U10") (pin "22") (pinfunction "IOVDD_22") (pintype "power_in"))
      (node (ref "U10") (pin "33") (pinfunction "IOVDD_33") (pintype "power_in"))
      (node (ref "U10") (pin "42") (pinfunction "IOVDD_42") (pintype "power_in"))
      (node (ref "U10") (pin "44") (pinfunction "VREG_VIN_44") (pintype "power_in"))
      (node (ref "U10") (pin "48") (pinfunction "USB_VDD_48") (pintype "power_in"))
      (node (ref "U10") (pin "49") (pinfunction "IOVDD_49") (pintype "power_in"))
      (node (ref "U11") (pin "1") (pinfunction "OUT_1") (pintype "power_in"))
      (node (ref "U3") (pin "2") (pinfunction "VLOGIC_2") (pintype "power_in"))
      (node (ref "U5") (pin "2") (pinfunction "VLOGIC_2") (pintype "power_in"))
      (node (ref "U7") (pin "2") (pinfunction "VLOGIC_2") (pintype "power_in"))
      (node (ref "U9") (pin "8") (pinfunction "VCC_8") (pintype "power_in"))
    )
    (net (code "139") (name "V3P3A") (class "Default")
      (node (ref "C111") (pin "1") (pinfunction "1_1") (pintype "passive"))
      (node (ref "C19") (pin "1") (pinfunction "1_1") (pintype "passive"))
      (node (ref "C27") (pin "1") (pinfunction "1_1") (pintype "passive"))
      (node (ref "C29") (pin "1") (pinfunction "1_1") (pintype "passive"))
      (node (ref "C40") (pin "1") (pinfunction "1_1") (pintype "passive"))
      (node (ref "C48") (pin "1") (pinfunction "1_1") (pintype "passive"))
      (node (ref "C50") (pin "1") (pinfunction "1_1") (pintype "passive"))
      (node (ref "C6") (pin "1") (pinfunction "1_1") (pintype "passive"))
      (node (ref "C61") (pin "1") (pinfunction "1_1") (pintype "passive"))
      (node (ref "C69") (pin "1") (pinfunction "1_1") (pintype "passive"))
      (node (ref "C71") (pin "1") (pinfunction "1_1") (pintype "passive"))
      (node (ref "C8") (pin "1") (pinfunction "1_1") (pintype "passive"))
      (node (ref "C82") (pin "1") (pinfunction "1_1") (pintype "passive"))
      (node (ref "C95") (pin "1") (pinfunction "1_1") (pintype "passive"))
      (node (ref "TP18") (pin "P$1") (pinfunction "P$1_P$1") (pintype "bidirectional"))
      (node (ref "U1") (pin "4") (pinfunction "VCC_4") (pintype "power_in"))
      (node (ref "U12") (pin "1") (pinfunction "OUT_1") (pintype "power_in"))
      (node (ref "U2") (pin "10") (pinfunction "+VS_10") (pintype "power_in"))
      (node (ref "U2") (pin "3") (pinfunction "+VS_3") (pintype "power_in"))
      (node (ref "U2") (pin "4") (pinfunction "+VS_4") (pintype "power_in"))
      (node (ref "U2") (pin "9") (pinfunction "+VS_9") (pintype "power_in"))
      (node (ref "U3") (pin "4") (pinfunction "VCC_4") (pintype "power_in"))
      (node (ref "U4") (pin "10") (pinfunction "+VS_10") (pintype "power_in"))
      (node (ref "U4") (pin "3") (pinfunction "+VS_3") (pintype "power_in"))
      (node (ref "U4") (pin "4") (pinfunction "+VS_4") (pintype "power_in"))
      (node (ref "U4") (pin "9") (pinfunction "+VS_9") (pintype "power_in"))
      (node (ref "U5") (pin "4") (pinfunction "VCC_4") (pintype "power_in"))
      (node (ref "U6") (pin "10") (pinfunction "+VS_10") (pintype "power_in"))
      (node (ref "U6") (pin "3") (pinfunction "+VS_3") (pintype "power_in"))
      (node (ref "U6") (pin "4") (pinfunction "+VS_4") (pintype "power_in"))
      (node (ref "U6") (pin "9") (pinfunction "+VS_9") (pintype "power_in"))
      (node (ref "U7") (pin "4") (pinfunction "VCC_4") (pintype "power_in"))
      (node (ref "U8") (pin "10") (pinfunction "+VS_10") (pintype "power_in"))
      (node (ref "U8") (pin "3") (pinfunction "+VS_3") (pintype "power_in"))
      (node (ref "U8") (pin "4") (pinfunction "+VS_4") (pintype "power_in"))
      (node (ref "U8") (pin "9") (pinfunction "+VS_9") (pintype "power_in"))
    )
    (net (code "140") (name "V5P0") (class "Default")
      (node (ref "C88") (pin "1") (pinfunction "1_1") (pintype "passive"))
      (node (ref "C89") (pin "1") (pinfunction "1_1") (pintype "passive"))
      (node (ref "C94") (pin "1") (pinfunction "1_1") (pintype "passive"))
      (node (ref "D1") (pin "C") (pinfunction "C_C") (pintype "bidirectional"))
      (node (ref "D2") (pin "C") (pinfunction "C_C") (pintype "bidirectional"))
      (node (ref "TP22") (pin "P$1") (pinfunction "P$1_P$1") (pintype "bidirectional"))
      (node (ref "U11") (pin "5") (pinfunction "/SHDN_5") (pintype "input"))
      (node (ref "U11") (pin "8") (pinfunction "IN_8") (pintype "power_in"))
      (node (ref "U12") (pin "5") (pinfunction "/SHDN_5") (pintype "input"))
      (node (ref "U12") (pin "8") (pinfunction "IN_8") (pintype "power_in"))
    )
    (net (code "141") (name "V5P0_IN") (class "Default")
      (node (ref "D1") (pin "A") (pinfunction "A_A") (pintype "bidirectional"))
      (node (ref "J5") (pin "A1") (pinfunction "2_A1") (pintype "passive"))
      (node (ref "J5") (pin "A3") (pinfunction "6_A3") (pintype "passive"))
      (node (ref "J5") (pin "B1") (pinfunction "1_B1") (pintype "passive"))
      (node (ref "J5") (pin "B3") (pinfunction "5_B3") (pintype "passive"))
    )
    (net (code "142") (name "V6P5") (class "Default")
      (node (ref "C105") (pin "1") (pinfunction "1_1") (pintype "passive"))
      (node (ref "LF1") (pin "2") (pinfunction "P$2_2") (pintype "bidirectional"))
      (node (ref "R66") (pin "2") (pinfunction "2_2") (pintype "passive"))
      (node (ref "U13") (pin "1") (pinfunction "VOUT_1") (pintype "power_in"))
    )
    (net (code "143") (name "V9P0") (class "Default")
      (node (ref "C104") (pin "1") (pinfunction "1_1") (pintype "passive"))
      (node (ref "J5") (pin "A18") (pinfunction "36_A18") (pintype "passive"))
      (node (ref "U13") (pin "6") (pinfunction "VIN_6") (pintype "power_in"))
    )
    (net (code "144") (name "VBUS") (class "Default")
      (node (ref "D2") (pin "A") (pinfunction "A_A") (pintype "bidirectional"))
      (node (ref "J4") (pin "1") (pinfunction "1_1") (pintype "bidirectional"))
    )
    (net (code "145") (name "VN1P2") (class "Default")
      (node (ref "C10") (pin "1") (pinfunction "1_1") (pintype "passive"))
      (node (ref "C107") (pin "2") (pinfunction "2_2") (pintype "passive"))
      (node (ref "C112") (pin "2") (pinfunction "2_2") (pintype "passive"))
      (node (ref "C21") (pin "1") (pinfunction "1_1") (pintype "passive"))
      (node (ref "C31") (pin "1") (pinfunction "1_1") (pintype "passive"))
      (node (ref "C42") (pin "1") (pinfunction "1_1") (pintype "passive"))
      (node (ref "C52") (pin "1") (pinfunction "1_1") (pintype "passive"))
      (node (ref "C63") (pin "1") (pinfunction "1_1") (pintype "passive"))
      (node (ref "C73") (pin "1") (pinfunction "1_1") (pintype "passive"))
      (node (ref "C84") (pin "1") (pinfunction "1_1") (pintype "passive"))
      (node (ref "TP19") (pin "P$1") (pinfunction "P$1_P$1") (pintype "bidirectional"))
      (node (ref "U14") (pin "1") (pinfunction "OUT_1") (pintype "bidirectional"))
      (node (ref "U14") (pin "2") (pinfunction "NC/ADJ_2") (pintype "bidirectional"))
      (node (ref "U2") (pin "15") (pinfunction "-VS_15") (pintype "power_in"))
      (node (ref "U2") (pin "16") (pinfunction "-VS_16") (pintype "power_in"))
      (node (ref "U2") (pin "21") (pinfunction "-VS_21") (pintype "power_in"))
      (node (ref "U2") (pin "22") (pinfunction "-VS_22") (pintype "power_in"))
      (node (ref "U4") (pin "15") (pinfunction "-VS_15") (pintype "power_in"))
      (node (ref "U4") (pin "16") (pinfunction "-VS_16") (pintype "power_in"))
      (node (ref "U4") (pin "21") (pinfunction "-VS_21") (pintype "power_in"))
      (node (ref "U4") (pin "22") (pinfunction "-VS_22") (pintype "power_in"))
      (node (ref "U6") (pin "15") (pinfunction "-VS_15") (pintype "power_in"))
      (node (ref "U6") (pin "16") (pinfunction "-VS_16") (pintype "power_in"))
      (node (ref "U6") (pin "21") (pinfunction "-VS_21") (pintype "power_in"))
      (node (ref "U6") (pin "22") (pinfunction "-VS_22") (pintype "power_in"))
      (node (ref "U8") (pin "15") (pinfunction "-VS_15") (pintype "power_in"))
      (node (ref "U8") (pin "16") (pinfunction "-VS_16") (pintype "power_in"))
      (node (ref "U8") (pin "21") (pinfunction "-VS_21") (pintype "power_in"))
      (node (ref "U8") (pin "22") (pinfunction "-VS_22") (pintype "power_in"))
    )
    (net (code "146") (name "VN3P0") (class "Default")
      (node (ref "C106") (pin "2") (pinfunction "2_2") (pintype "passive"))
      (node (ref "J5") (pin "A19") (pinfunction "38_A19") (pintype "passive"))
      (node (ref "U14") (pin "3") (pinfunction "EN_3") (pintype "bidirectional"))
      (node (ref "U14") (pin "6") (pinfunction "IN_6") (pintype "bidirectional"))
      (node (ref "U14") (pin "PAD") (pinfunction "IN_PAD") (pintype "bidirectional"))
    )
    (net (code "147") (name "VN20P0") (class "Default")
      (node (ref "C109") (pin "2") (pinfunction "2_2") (pintype "passive"))
      (node (ref "C110") (pin "2") (pinfunction "2_2") (pintype "passive"))
      (node (ref "LF2") (pin "2") (pinfunction "P$2_2") (pintype "bidirectional"))
      (node (ref "R69") (pin "1") (pinfunction "1_1") (pintype "passive"))
      (node (ref "U15") (pin "1") (pinfunction "OUT_1") (pintype "bidirectional"))
    )
    (net (code "148") (name "VN22") (class "Default")
      (node (ref "C108") (pin "2") (pinfunction "2_2") (pintype "passive"))
      (node (ref "J5") (pin "B20") (pinfunction "39_B20") (pintype "passive"))
      (node (ref "U15") (pin "6") (pinfunction "IN_6") (pintype "bidirectional"))
      (node (ref "U15") (pin "PAD") (pinfunction "IN_PAD") (pintype "bidirectional"))
    )
    (net (code "149") (name "VOCM_A1") (class "Default")
      (node (ref "C20") (pin "1") (pinfunction "1_1") (pintype "passive"))
      (node (ref "C9") (pin "1") (pinfunction "1_1") (pintype "passive"))
      (node (ref "R13") (pin "1") (pinfunction "1_1") (pintype "passive"))
      (node (ref "R14") (pin "2") (pinfunction "2_2") (pintype "passive"))
      (node (ref "TP5") (pin "P$1") (pinfunction "P$1_P$1") (pintype "bidirectional"))
      (node (ref "U2") (pin "11") (pinfunction "VOCM_11") (pintype "input"))
      (node (ref "U2") (pin "17") (pinfunction "VOCM_17") (pintype "input"))
    )
    (net (code "150") (name "VOCM_A2") (class "Default")
      (node (ref "C30") (pin "1") (pinfunction "1_1") (pintype "passive"))
      (node (ref "C41") (pin "1") (pinfunction "1_1") (pintype "passive"))
      (node (ref "R27") (pin "1") (pinfunction "1_1") (pintype "passive"))
      (node (ref "R28") (pin "2") (pinfunction "2_2") (pintype "passive"))
      (node (ref "TP8") (pin "P$1") (pinfunction "P$1_P$1") (pintype "bidirectional"))
      (node (ref "U4") (pin "11") (pinfunction "VOCM_11") (pintype "input"))
      (node (ref "U4") (pin "17") (pinfunction "VOCM_17") (pintype "input"))
    )
    (net (code "151") (name "VOCM_A3") (class "Default")
      (node (ref "C51") (pin "1") (pinfunction "1_1") (pintype "passive"))
      (node (ref "C62") (pin "1") (pinfunction "1_1") (pintype "passive"))
      (node (ref "R41") (pin "1") (pinfunction "1_1") (pintype "passive"))
      (node (ref "R42") (pin "2") (pinfunction "2_2") (pintype "passive"))
      (node (ref "TP12") (pin "P$1") (pinfunction "P$1_P$1") (pintype "bidirectional"))
      (node (ref "U6") (pin "11") (pinfunction "VOCM_11") (pintype "input"))
      (node (ref "U6") (pin "17") (pinfunction "VOCM_17") (pintype "input"))
    )
    (net (code "152") (name "VOCM_A4") (class "Default")
      (node (ref "C72") (pin "1") (pinfunction "1_1") (pintype "passive"))
      (node (ref "C83") (pin "1") (pinfunction "1_1") (pintype "passive"))
      (node (ref "R55") (pin "1") (pinfunction "1_1") (pintype "passive"))
      (node (ref "R56") (pin "2") (pinfunction "2_2") (pintype "passive"))
      (node (ref "TP16") (pin "P$1") (pinfunction "P$1_P$1") (pintype "bidirectional"))
      (node (ref "U8") (pin "11") (pinfunction "VOCM_11") (pintype "input"))
      (node (ref "U8") (pin "17") (pinfunction "VOCM_17") (pintype "input"))
    )
    (net (code "153") (name "unconnected-(J1-Pad34)") (class "Default")
      (node (ref "J1") (pin "34") (pinfunction "34_34") (pintype "passive"))
    )
    (net (code "154") (name "unconnected-(J4-Pad4)") (class "Default")
      (node (ref "J4") (pin "4") (pinfunction "4_4") (pintype "bidirectional"))
    )
    (net (code "155") (name "unconnected-(U2A-{slash}DISABLE-Pad20)") (class "Default")
      (node (ref "U2") (pin "20") (pinfunction "/DISABLE_20") (pintype "input"))
    )
    (net (code "156") (name "unconnected-(U2B-{slash}DISABLE-Pad14)") (class "Default")
      (node (ref "U2") (pin "14") (pinfunction "/DISABLE_14") (pintype "input"))
    )
    (net (code "157") (name "unconnected-(U4A-{slash}DISABLE-Pad20)") (class "Default")
      (node (ref "U4") (pin "20") (pinfunction "/DISABLE_20") (pintype "input"))
    )
    (net (code "158") (name "unconnected-(U4B-{slash}DISABLE-Pad14)") (class "Default")
      (node (ref "U4") (pin "14") (pinfunction "/DISABLE_14") (pintype "input"))
    )
    (net (code "159") (name "unconnected-(U6A-{slash}DISABLE-Pad20)") (class "Default")
      (node (ref "U6") (pin "20") (pinfunction "/DISABLE_20") (pintype "input"))
    )
    (net (code "160") (name "unconnected-(U6B-{slash}DISABLE-Pad14)") (class "Default")
      (node (ref "U6") (pin "14") (pinfunction "/DISABLE_14") (pintype "input"))
    )
    (net (code "161") (name "unconnected-(U8A-{slash}DISABLE-Pad20)") (class "Default")
      (node (ref "U8") (pin "20") (pinfunction "/DISABLE_20") (pintype "input"))
    )
    (net (code "162") (name "unconnected-(U8B-{slash}DISABLE-Pad14)") (class "Default")
      (node (ref "U8") (pin "14") (pinfunction "/DISABLE_14") (pintype "input"))
    )
    (net (code "163") (name "unconnected-(U11-PWRGD-Pad2)") (class "Default")
      (node (ref "U11") (pin "2") (pinfunction "PWRGD_2") (pintype "output"))
    )
    (net (code "164") (name "unconnected-(U12-PWRGD-Pad2)") (class "Default")
      (node (ref "U12") (pin "2") (pinfunction "PWRGD_2") (pintype "output"))
    )
    (net (code "165") (name "unconnected-(U13-SS-Pad5)") (class "Default")
      (node (ref "U13") (pin "5") (pinfunction "SS_5") (pintype "bidirectional"))
    )
    (net (code "166") (name "{slash}CS_A1") (class "Default")
      (node (ref "U1") (pin "12") (pinfunction "/CS_12") (pintype "input"))
      (node (ref "U10") (pin "27") (pinfunction "GPIO16_27") (pintype "bidirectional"))
    )
    (net (code "167") (name "{slash}CS_A2") (class "Default")
      (node (ref "U10") (pin "37") (pinfunction "GPIO25_37") (pintype "bidirectional"))
      (node (ref "U3") (pin "12") (pinfunction "/CS_12") (pintype "input"))
    )
    (net (code "168") (name "{slash}CS_A3") (class "Default")
      (node (ref "J2") (pin "2") (pinfunction "2_2") (pintype "passive"))
      (node (ref "U10") (pin "15") (pinfunction "GPIO12_15") (pintype "bidirectional"))
      (node (ref "U5") (pin "12") (pinfunction "/CS_12") (pintype "input"))
    )
    (net (code "169") (name "{slash}CS_A4") (class "Default")
      (node (ref "U10") (pin "32") (pinfunction "GPIO21_32") (pintype "bidirectional"))
      (node (ref "U7") (pin "12") (pinfunction "/CS_12") (pintype "input"))
    )
  )
)
